# Daughter_Card_Schematic_v5.net
KiCad netlist of a schematic drawn in EAGLE
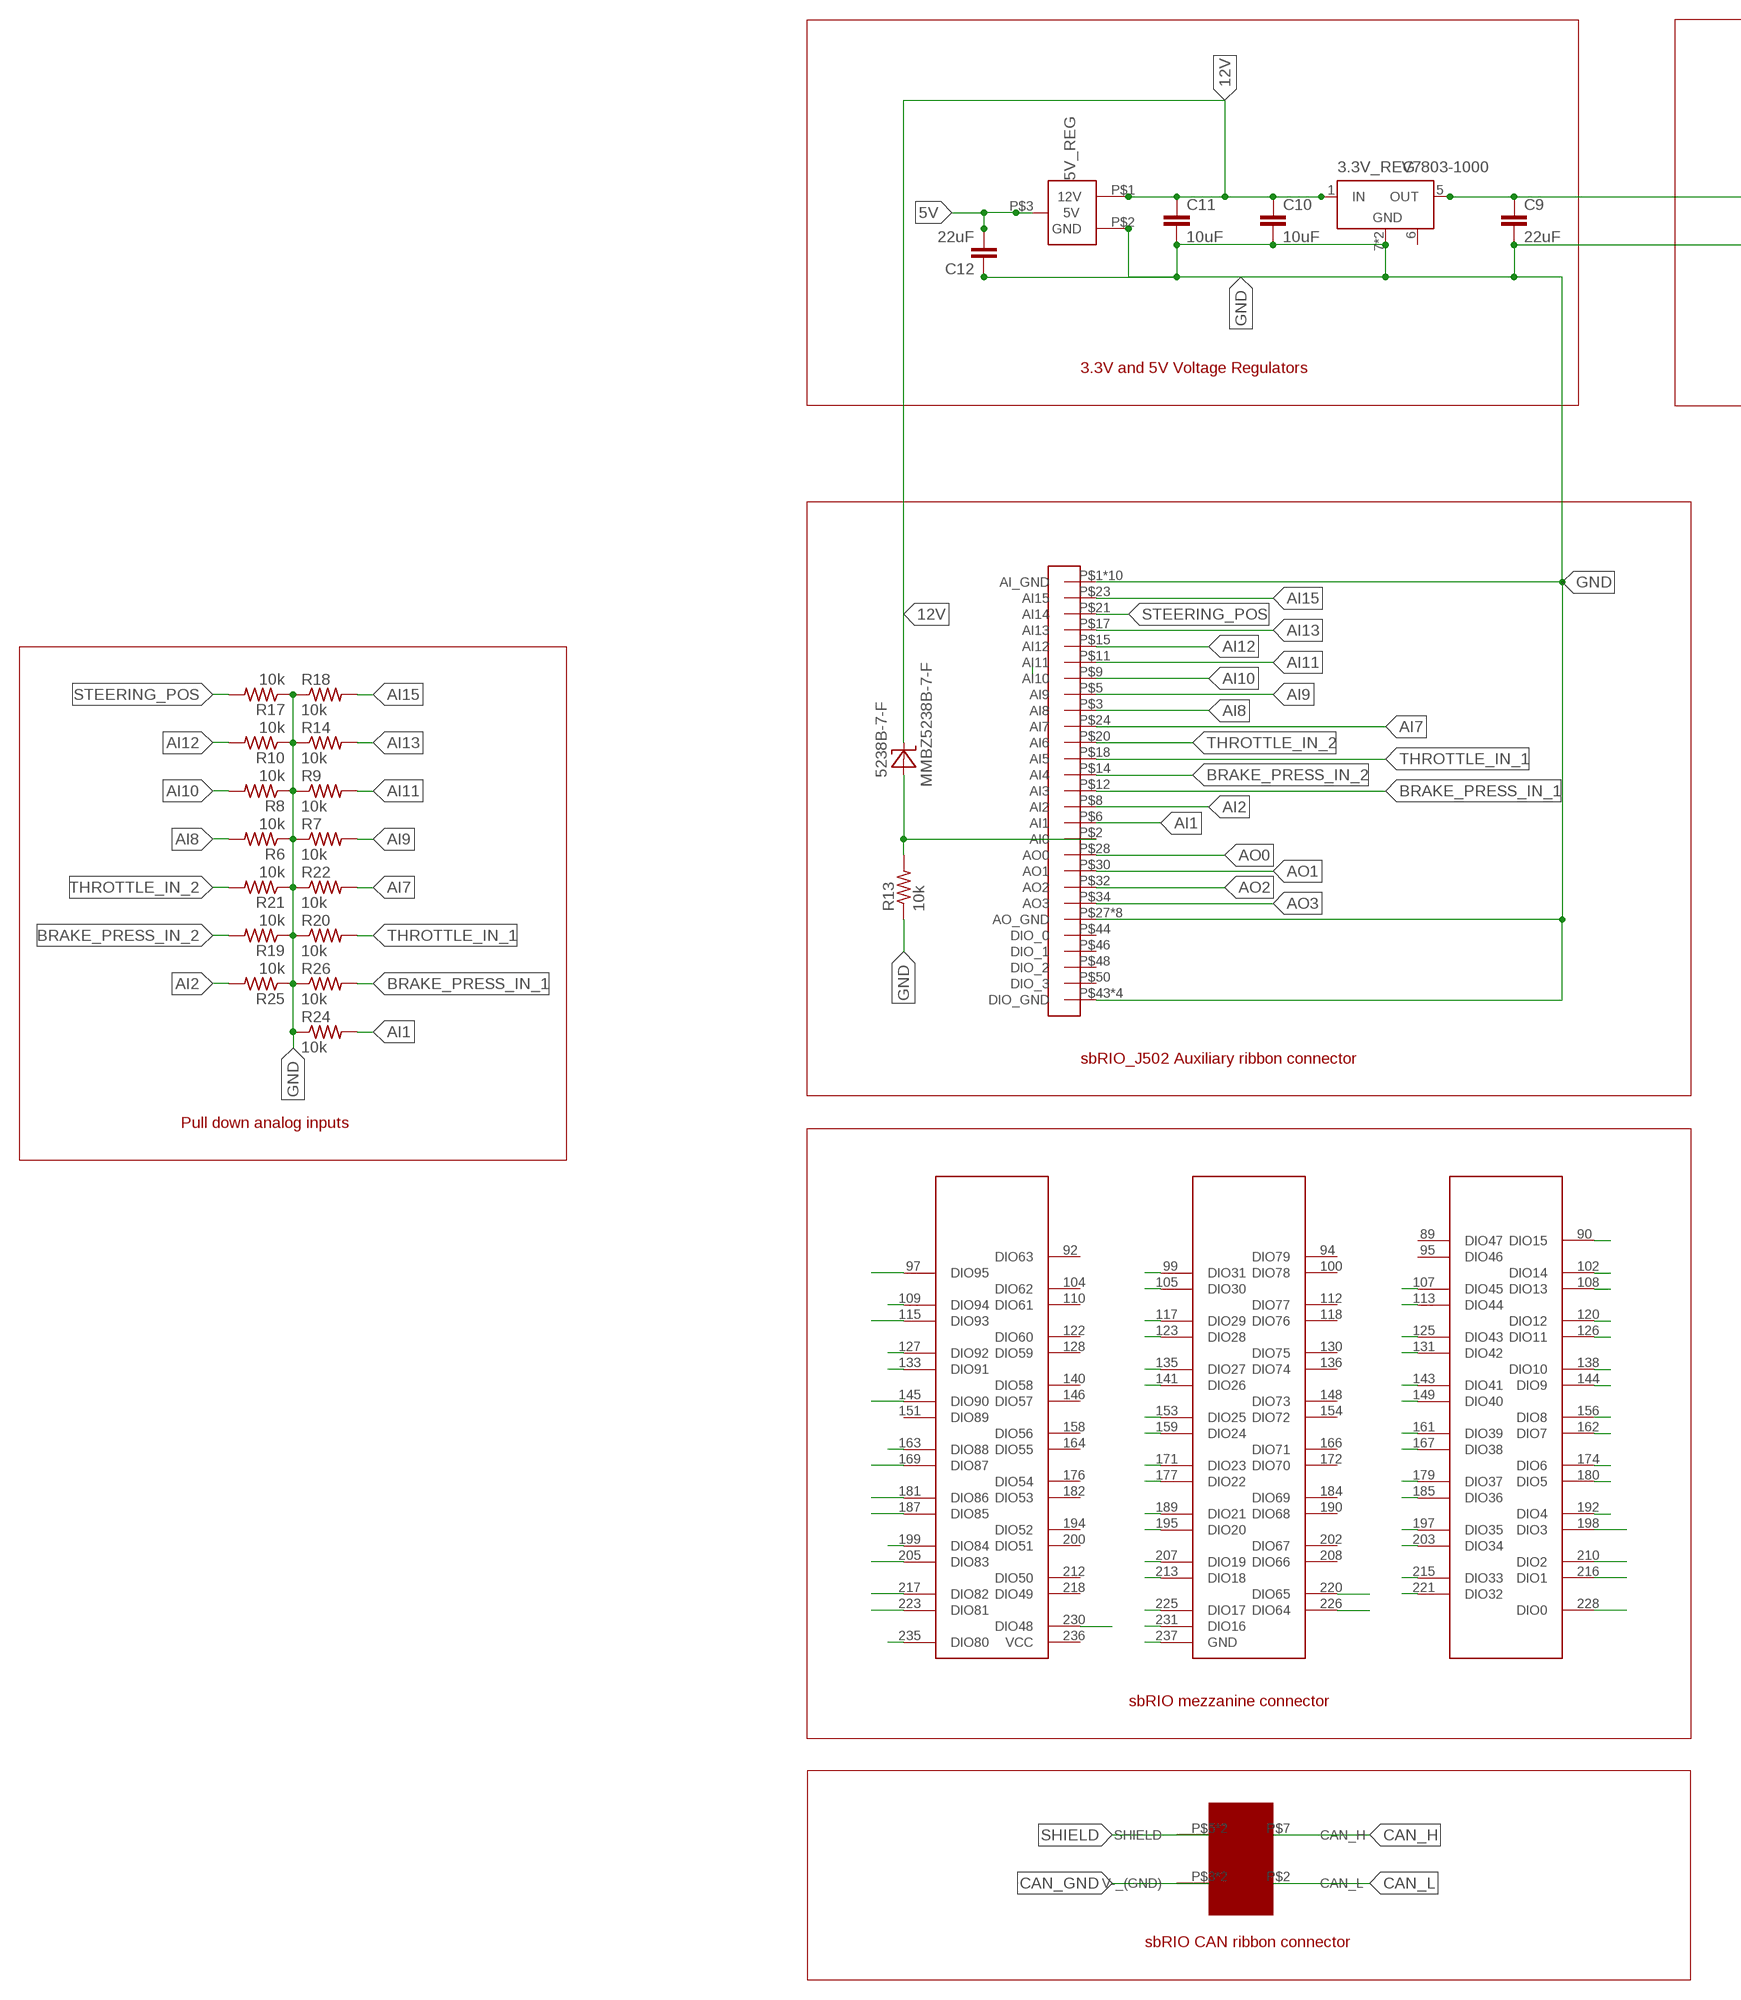
[diagram p0: schematic, sheet 1, part 1 of 2]
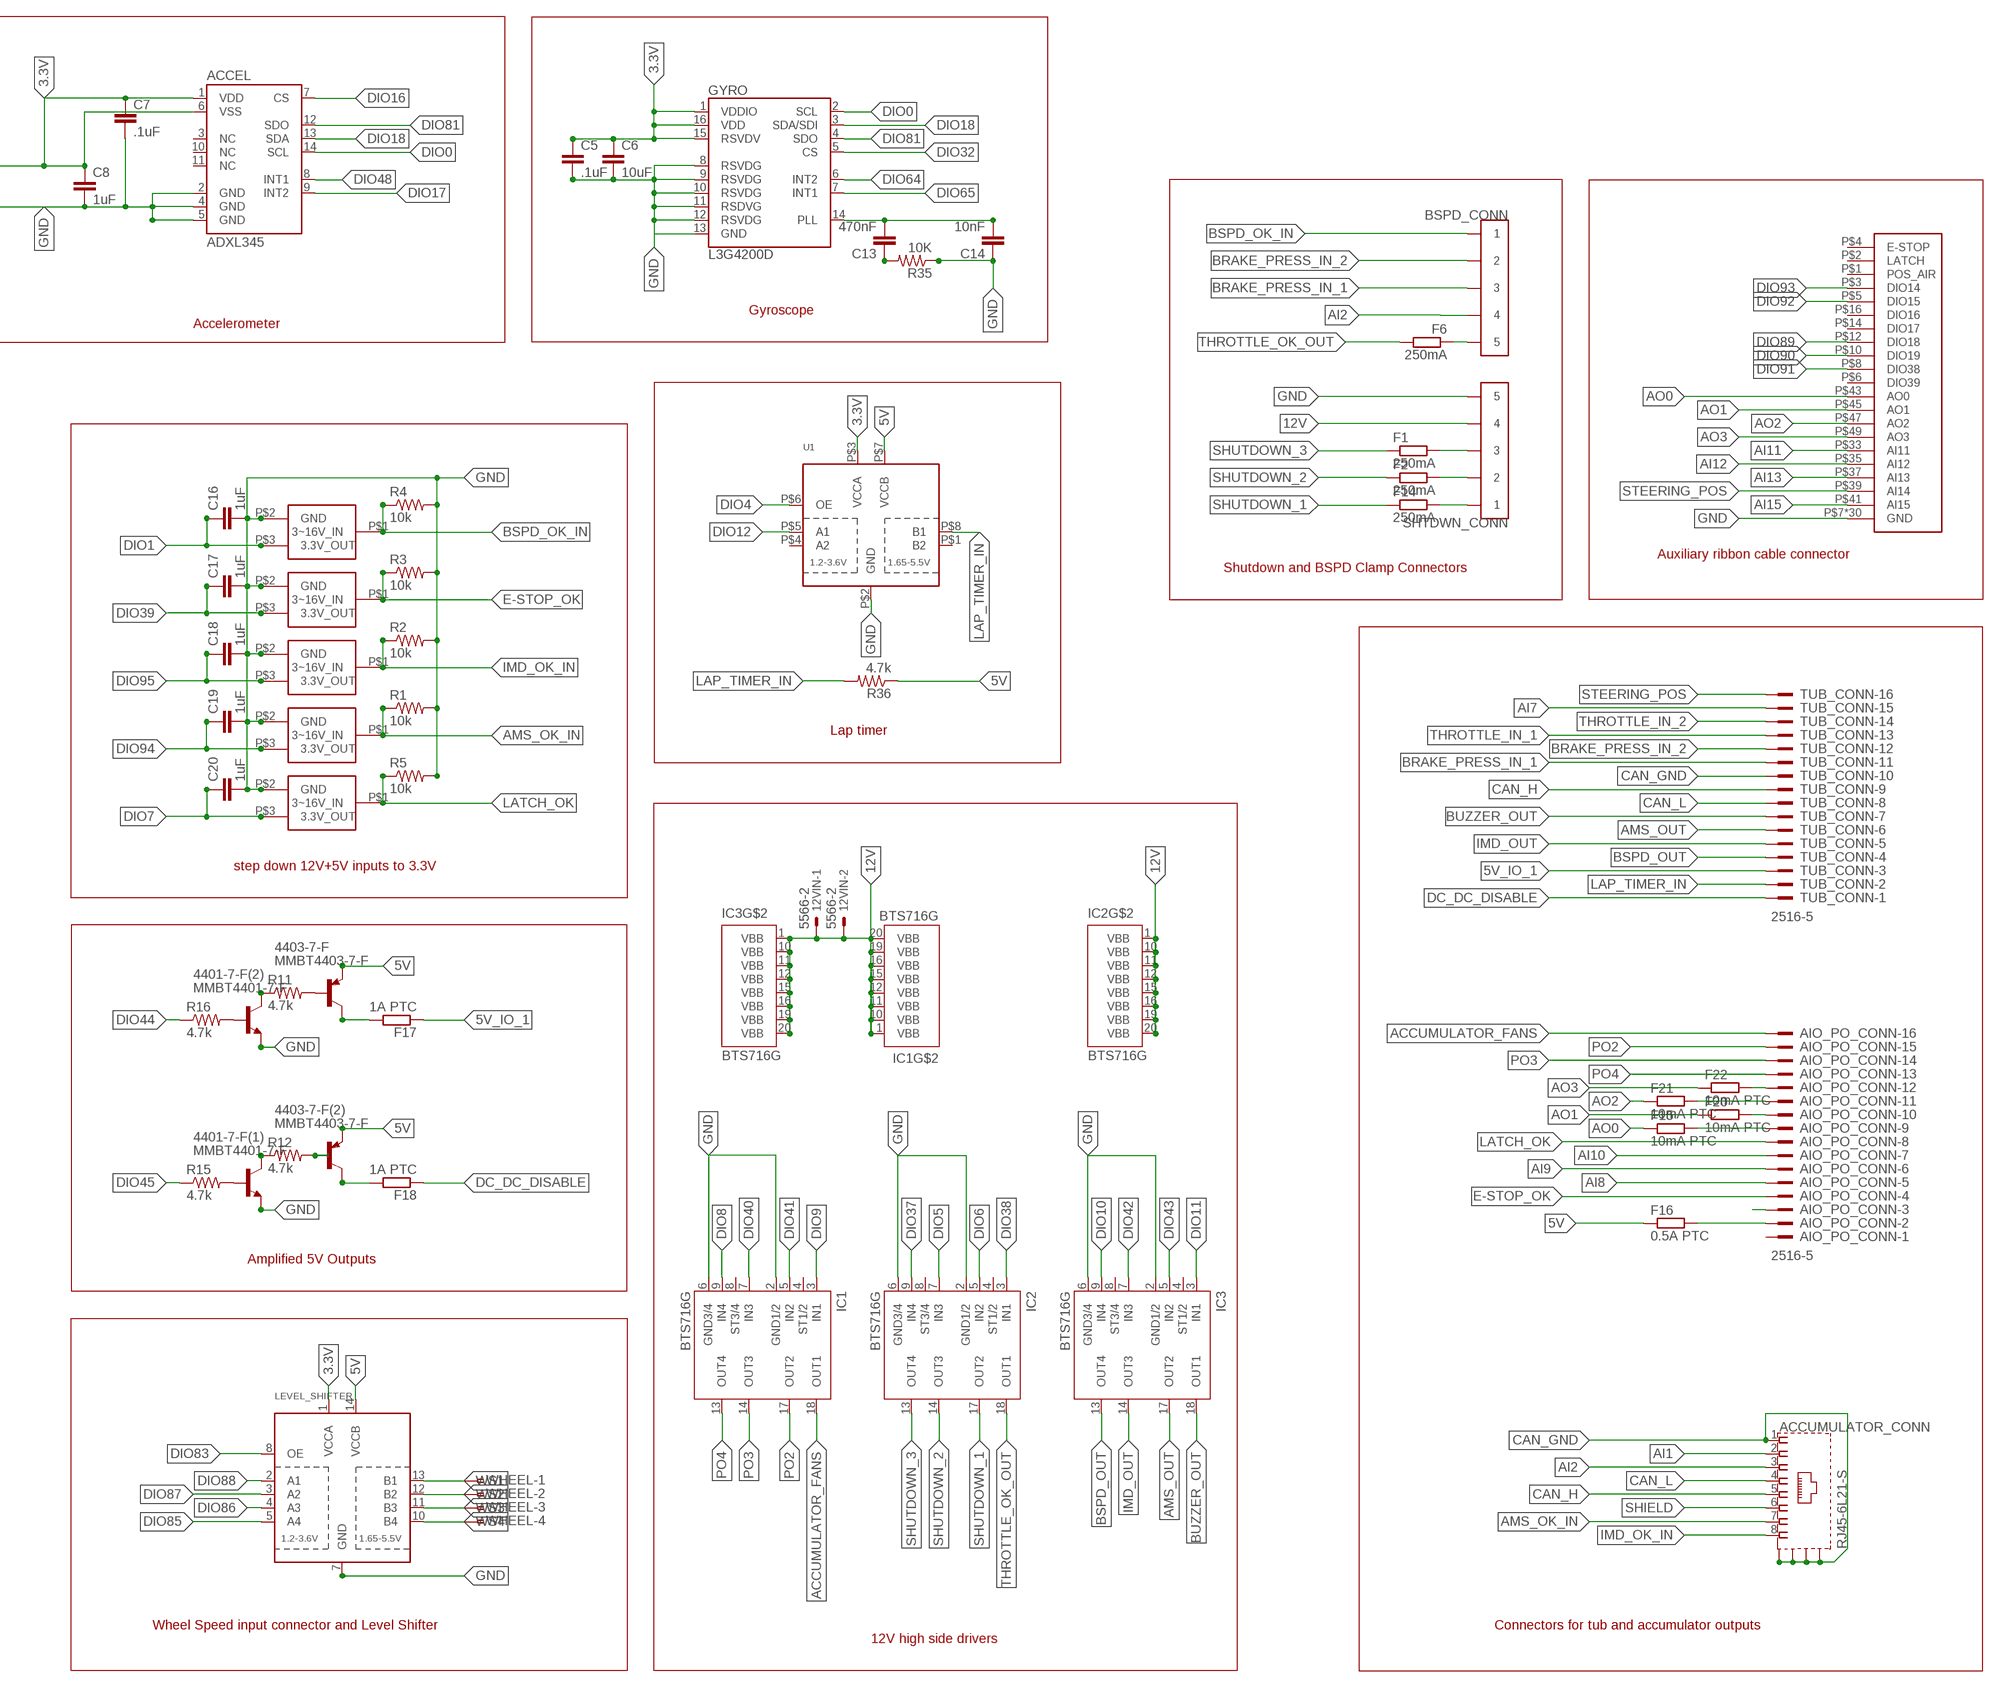
[diagram p1: schematic, sheet 1, part 2 of 2]

(export (version "E")
  (design (tool "Eeschema 10.0.6"))
  (components
    (comp (ref "3.3V_REG")
      (value "V7803-1000")
      (footprint "eagle-import:V78XX-1000")
      (libsource (lib "eagle-import") (part "V7803-1000"))
    )
    (comp (ref "5V_REG")
      (value "V78XX-1500")
      (footprint "eagle-import:V78XX-1500R")
      (libsource (lib "eagle-import") (part "V78XX-1500"))
    )
    (comp (ref "12VIN")
      (value "5566-2")
      (footprint "eagle-import:5566-2")
      (libsource (lib "eagle-import") (part "5566-2"))
    )
    (comp (ref "4401-7-F(1)")
      (value "MMBT4401-7-F")
      (footprint "eagle-import:SOT-23-3")
      (libsource (lib "eagle-import") (part "MMBT4401-7-F"))
    )
    (comp (ref "4401-7-F(2)")
      (value "MMBT4401-7-F")
      (footprint "eagle-import:SOT-23-3")
      (libsource (lib "eagle-import") (part "MMBT4401-7-F"))
    )
    (comp (ref "4403-7-F")
      (value "MMBT4403-7-F")
      (footprint "eagle-import:SOT-23-3")
      (libsource (lib "eagle-import") (part "MMBT4403-7-F"))
    )
    (comp (ref "4403-7-F(2)")
      (value "MMBT4403-7-F")
      (footprint "eagle-import:SOT-23-3")
      (libsource (lib "eagle-import") (part "MMBT4403-7-F"))
    )
    (comp (ref "5225-3.3M5-TR(5)")
      (value "MIC5225-3.3YM5-TR")
      (footprint "eagle-import:SOT-23-3")
      (libsource (lib "eagle-import") (part "MIC5225-3.3YM5-TR"))
    )
    (comp (ref "5238B-7-F")
      (value "MMBZ5238B-7-F")
      (footprint "eagle-import:SOT-23-3")
      (libsource (lib "eagle-import") (part "MMBZ5238B-7-F"))
    )
    (comp (ref "5525-3.3YM5-TR(1)")
      (value "MIC5225-3.3YM5-TR")
      (footprint "eagle-import:SOT-23-3")
      (libsource (lib "eagle-import") (part "MIC5225-3.3YM5-TR"))
    )
    (comp (ref "5525-3.3YM5-TR(2)")
      (value "MIC5225-3.3YM5-TR")
      (footprint "eagle-import:SOT-23-3")
      (libsource (lib "eagle-import") (part "MIC5225-3.3YM5-TR"))
    )
    (comp (ref "5525-3.3YM5-TR(3)")
      (value "MIC5225-3.3YM5-TR")
      (footprint "eagle-import:SOT-23-3")
      (libsource (lib "eagle-import") (part "MIC5225-3.3YM5-TR"))
    )
    (comp (ref "5525-3.3YM5-TR(4)")
      (value "MIC5225-3.3YM5-TR")
      (footprint "eagle-import:SOT-23-3")
      (libsource (lib "eagle-import") (part "MIC5225-3.3YM5-TR"))
    )
    (comp (ref "ACCEL")
      (value "ADXL345")
      (footprint "eagle-import:LGA14")
      (libsource (lib "eagle-import") (part "ADXL345"))
    )
    (comp (ref "ACCUMULATOR_CONN")
      (value "RJ45-6L21-S")
      (footprint "eagle-import:RJ45-SHIELD1")
      (libsource (lib "eagle-import") (part "RJ4521-S-6L"))
    )
    (comp (ref "AIO_PO_CONN")
      (value "2516-5")
      (footprint "eagle-import:PAK100_2500-5-16")
      (fields (field (name "MPN") "D2516-5002-AR"))
      (libsource (lib "eagle-import") (part "2516-5"))
    )
    (comp (ref "BSPD_CONN")
      (value "CONN_5")
      (footprint "eagle-import:CONNECTOR_5")
      (libsource (lib "eagle-import") (part "CONN_5"))
    )
    (comp (ref "C5")
      (value ".1uF")
      (footprint "eagle-import:0603-CAP")
      (libsource (lib "eagle-import") (part "CAP0603-CAP"))
    )
    (comp (ref "C6")
      (value "10uF")
      (footprint "eagle-import:0603-CAP")
      (libsource (lib "eagle-import") (part "CAP0603-CAP"))
    )
    (comp (ref "C7")
      (value ".1uF")
      (footprint "eagle-import:0603-CAP")
      (libsource (lib "eagle-import") (part "CAP0603-CAP"))
    )
    (comp (ref "C8")
      (value "1uF")
      (footprint "eagle-import:0603-CAP")
      (libsource (lib "eagle-import") (part "CAP0603-CAP"))
    )
    (comp (ref "C9")
      (value "22uF")
      (footprint "eagle-import:0603-CAP")
      (libsource (lib "eagle-import") (part "CAP0603-CAP"))
    )
    (comp (ref "C10")
      (value "10uF")
      (footprint "eagle-import:0603-CAP")
      (libsource (lib "eagle-import") (part "CAP0603-CAP"))
    )
    (comp (ref "C11")
      (value "10uF")
      (footprint "eagle-import:0603-CAP")
      (libsource (lib "eagle-import") (part "CAP0603-CAP"))
    )
    (comp (ref "C12")
      (value "22uF")
      (footprint "eagle-import:0603-CAP")
      (libsource (lib "eagle-import") (part "CAP0603-CAP"))
    )
    (comp (ref "C13")
      (value "470nF")
      (footprint "eagle-import:0603-CAP")
      (libsource (lib "eagle-import") (part "CAP0603-CAP"))
    )
    (comp (ref "C14")
      (value "10nF")
      (footprint "eagle-import:0603-CAP")
      (libsource (lib "eagle-import") (part "CAP0603-CAP"))
    )
    (comp (ref "C16")
      (value "1uF")
      (footprint "eagle-import:0603-CAP")
      (libsource (lib "eagle-import") (part "CAP0603-CAP"))
    )
    (comp (ref "C17")
      (value "1uF")
      (footprint "eagle-import:0603-CAP")
      (libsource (lib "eagle-import") (part "CAP0603-CAP"))
    )
    (comp (ref "C18")
      (value "1uF")
      (footprint "eagle-import:0603-CAP")
      (libsource (lib "eagle-import") (part "CAP0603-CAP"))
    )
    (comp (ref "C19")
      (value "1uF")
      (footprint "eagle-import:0603-CAP")
      (libsource (lib "eagle-import") (part "CAP0603-CAP"))
    )
    (comp (ref "C20")
      (value "1uF")
      (footprint "eagle-import:0603-CAP")
      (libsource (lib "eagle-import") (part "CAP0603-CAP"))
    )
    (comp (ref "F1")
      (value "250mA")
      (footprint "eagle-import:R0603")
      (libsource (lib "eagle-import") (part "R-EU_R0603"))
    )
    (comp (ref "F2")
      (value "250mA")
      (footprint "eagle-import:R0603")
      (libsource (lib "eagle-import") (part "R-EU_R0603"))
    )
    (comp (ref "F6")
      (value "250mA")
      (footprint "eagle-import:R0603")
      (libsource (lib "eagle-import") (part "R-EU_R0603"))
    )
    (comp (ref "F14")
      (value "250mA")
      (footprint "eagle-import:R0603")
      (libsource (lib "eagle-import") (part "R-EU_R0603"))
    )
    (comp (ref "F15")
      (value "10mA PTC")
      (footprint "eagle-import:R0402")
      (libsource (lib "eagle-import") (part "R-EU_R0402"))
    )
    (comp (ref "F16")
      (value "0.5A PTC")
      (footprint "eagle-import:R0603")
      (libsource (lib "eagle-import") (part "R-EU_R0603"))
    )
    (comp (ref "F17")
      (value "1A PTC")
      (footprint "eagle-import:R0603")
      (libsource (lib "eagle-import") (part "R-EU_R0603"))
    )
    (comp (ref "F18")
      (value "1A PTC")
      (footprint "eagle-import:R0603")
      (libsource (lib "eagle-import") (part "R-EU_R0603"))
    )
    (comp (ref "F20")
      (value "10mA PTC")
      (footprint "eagle-import:R0402")
      (libsource (lib "eagle-import") (part "R-EU_R0402"))
    )
    (comp (ref "F21")
      (value "10mA PTC")
      (footprint "eagle-import:R0402")
      (libsource (lib "eagle-import") (part "R-EU_R0402"))
    )
    (comp (ref "F22")
      (value "10mA PTC")
      (footprint "eagle-import:R0402")
      (libsource (lib "eagle-import") (part "R-EU_R0402"))
    )
    (comp (ref "GYRO")
      (value "L3G4200D")
      (footprint "eagle-import:LGA16-4X4")
      (libsource (lib "eagle-import") (part "L3G4200D"))
    )
    (comp (ref "IC1")
      (value "BTS716G")
      (footprint "eagle-import:PG-DSO-20")
      (libsource (lib "eagle-import") (part "BTS716G"))
    )
    (comp (ref "IC2")
      (value "BTS716G")
      (footprint "eagle-import:PG-DSO-20")
      (libsource (lib "eagle-import") (part "BTS716G"))
    )
    (comp (ref "IC3")
      (value "BTS716G")
      (footprint "eagle-import:PG-DSO-20")
      (libsource (lib "eagle-import") (part "BTS716G"))
    )
    (comp (ref "LEVEL_SHIFTER")
      (value "TXB0104PWR")
      (footprint "eagle-import:TSSOP14")
      (libsource (lib "eagle-import") (part "TXB0104PWR"))
    )
    (comp (ref "R1")
      (value "10k")
      (footprint "eagle-import:R0402")
      (libsource (lib "eagle-import") (part "R-US_R0402"))
    )
    (comp (ref "R2")
      (value "10k")
      (footprint "eagle-import:R0402")
      (libsource (lib "eagle-import") (part "R-US_R0402"))
    )
    (comp (ref "R3")
      (value "10k")
      (footprint "eagle-import:R0402")
      (libsource (lib "eagle-import") (part "R-US_R0402"))
    )
    (comp (ref "R4")
      (value "10k")
      (footprint "eagle-import:R0402")
      (libsource (lib "eagle-import") (part "R-US_R0402"))
    )
    (comp (ref "R5")
      (value "10k")
      (footprint "eagle-import:R0402")
      (libsource (lib "eagle-import") (part "R-US_R0402"))
    )
    (comp (ref "R6")
      (value "10k")
      (footprint "eagle-import:R0402")
      (libsource (lib "eagle-import") (part "R-US_R0402"))
    )
    (comp (ref "R7")
      (value "10k")
      (footprint "eagle-import:R0402")
      (libsource (lib "eagle-import") (part "R-US_R0402"))
    )
    (comp (ref "R8")
      (value "10k")
      (footprint "eagle-import:R0402")
      (libsource (lib "eagle-import") (part "R-US_R0402"))
    )
    (comp (ref "R9")
      (value "10k")
      (footprint "eagle-import:R0402")
      (libsource (lib "eagle-import") (part "R-US_R0402"))
    )
    (comp (ref "R10")
      (value "10k")
      (footprint "eagle-import:R0402")
      (libsource (lib "eagle-import") (part "R-US_R0402"))
    )
    (comp (ref "R11")
      (value "4.7k")
      (footprint "eagle-import:R0402")
      (libsource (lib "eagle-import") (part "R-US_R0402"))
    )
    (comp (ref "R12")
      (value "4.7k")
      (footprint "eagle-import:R0402")
      (libsource (lib "eagle-import") (part "R-US_R0402"))
    )
    (comp (ref "R13")
      (value "10k")
      (footprint "eagle-import:R0402")
      (libsource (lib "eagle-import") (part "R-US_R0402"))
    )
    (comp (ref "R14")
      (value "10k")
      (footprint "eagle-import:R0402")
      (libsource (lib "eagle-import") (part "R-US_R0402"))
    )
    (comp (ref "R15")
      (value "4.7k")
      (footprint "eagle-import:R0402")
      (libsource (lib "eagle-import") (part "R-US_R0402"))
    )
    (comp (ref "R16")
      (value "4.7k")
      (footprint "eagle-import:R0402")
      (libsource (lib "eagle-import") (part "R-US_R0402"))
    )
    (comp (ref "R17")
      (value "10k")
      (footprint "eagle-import:R0402")
      (libsource (lib "eagle-import") (part "R-US_R0402"))
    )
    (comp (ref "R18")
      (value "10k")
      (footprint "eagle-import:R0402")
      (libsource (lib "eagle-import") (part "R-US_R0402"))
    )
    (comp (ref "R19")
      (value "10k")
      (footprint "eagle-import:R0402")
      (libsource (lib "eagle-import") (part "R-US_R0402"))
    )
    (comp (ref "R20")
      (value "10k")
      (footprint "eagle-import:R0402")
      (libsource (lib "eagle-import") (part "R-US_R0402"))
    )
    (comp (ref "R21")
      (value "10k")
      (footprint "eagle-import:R0402")
      (libsource (lib "eagle-import") (part "R-US_R0402"))
    )
    (comp (ref "R22")
      (value "10k")
      (footprint "eagle-import:R0402")
      (libsource (lib "eagle-import") (part "R-US_R0402"))
    )
    (comp (ref "R24")
      (value "10k")
      (footprint "eagle-import:R0402")
      (libsource (lib "eagle-import") (part "R-US_R0402"))
    )
    (comp (ref "R25")
      (value "10k")
      (footprint "eagle-import:R0402")
      (libsource (lib "eagle-import") (part "R-US_R0402"))
    )
    (comp (ref "R26")
      (value "10k")
      (footprint "eagle-import:R0402")
      (libsource (lib "eagle-import") (part "R-US_R0402"))
    )
    (comp (ref "R35")
      (value "10K")
      (footprint "eagle-import:0603-RES")
      (libsource (lib "eagle-import") (part "RESISTOR0603-RES"))
    )
    (comp (ref "R36")
      (value "4.7k")
      (footprint "eagle-import:R0402")
      (libsource (lib "eagle-import") (part "R-US_R0402"))
    )
    (comp (ref "SBRIO_ANALOG")
      (value "SBRIO_MIO")
      (footprint "eagle-import:SBRIO_J502_J503")
      (libsource (lib "eagle-import") (part "SBRIO_MIO"))
    )
    (comp (ref "SBRIO_AUX")
      (value "SBRIO_AUX")
      (footprint "eagle-import:SBRIO_J502_J503")
      (libsource (lib "eagle-import") (part "SBRIO_AUX"))
    )
    (comp (ref "SBRIO_CAN")
      (value "SBRIO_W500")
      (footprint "eagle-import:SBRIO_W")
      (libsource (lib "eagle-import") (part "SBRIO_W500"))
    )
    (comp (ref "SBRIO_MEZZANINE")
      (value "SBRIO_RMC")
      (footprint "eagle-import:SEAM-40-XX.X-XX-06-X-A")
      (libsource (lib "eagle-import") (part "SBRIO_RMC"))
    )
    (comp (ref "SHTDWN_CONN")
      (value "CONN_5")
      (footprint "eagle-import:CONNECTOR_5")
      (libsource (lib "eagle-import") (part "CONN_5"))
    )
    (comp (ref "TUB_CONN")
      (value "2516-5")
      (footprint "eagle-import:PAK100_2500-5-16")
      (fields (field (name "MPN") "D2516-5002-AR"))
      (libsource (lib "eagle-import") (part "2516-5"))
    )
    (comp (ref "U1")
      (value "TXS0102")
      (footprint "eagle-import:VFSOP-8")
      (libsource (lib "eagle-import") (part "TXS0102"))
    )
    (comp (ref "WHEEL")
      (value "FTOP-4")
      (footprint "eagle-import:FTOP-4")
      (libsource (lib "eagle-import") (part "FTOP-4"))
    )
  )
  (nets
    (net (code "1") (name "/VCC") (class "Default")
      (node (ref "SBRIO_MEZZANINE") (pin "236") (pinfunction "VCC_236") (pintype "power_in"))
    )
    (net (code "2") (name "3.3V") (class "Default")
      (node (ref "3.3V_REG") (pin "5") (pinfunction "OUT_5") (pintype "output"))
      (node (ref "ACCEL") (pin "1") (pinfunction "VDD_1") (pintype "bidirectional"))
      (node (ref "ACCEL") (pin "6") (pinfunction "VSS_6") (pintype "bidirectional"))
      (node (ref "C5") (pin "1") (pinfunction "1_1") (pintype "passive"))
      (node (ref "C6") (pin "1") (pinfunction "1_1") (pintype "passive"))
      (node (ref "C7") (pin "1") (pinfunction "1_1") (pintype "passive"))
      (node (ref "C8") (pin "1") (pinfunction "1_1") (pintype "passive"))
      (node (ref "C9") (pin "1") (pinfunction "1_1") (pintype "passive"))
      (node (ref "GYRO") (pin "1") (pinfunction "VDDIO_1") (pintype "bidirectional"))
      (node (ref "GYRO") (pin "15") (pinfunction "RSVDV_15") (pintype "bidirectional"))
      (node (ref "GYRO") (pin "16") (pinfunction "VDD_16") (pintype "bidirectional"))
      (node (ref "LEVEL_SHIFTER") (pin "1") (pinfunction "VCCA_1") (pintype "bidirectional"))
      (node (ref "U1") (pin "P$3") (pinfunction "VCCA_P$3") (pintype "bidirectional"))
    )
    (net (code "3") (name "5V") (class "Default")
      (node (ref "4403-7-F") (pin "P$3") (pinfunction "E_P$3") (pintype "passive"))
      (node (ref "4403-7-F(2)") (pin "P$3") (pinfunction "E_P$3") (pintype "passive"))
      (node (ref "5V_REG") (pin "P$3") (pinfunction "5V_P$3") (pintype "power_in"))
      (node (ref "C12") (pin "2") (pinfunction "2_2") (pintype "passive"))
      (node (ref "F16") (pin "1") (pinfunction "1_1") (pintype "passive"))
      (node (ref "LEVEL_SHIFTER") (pin "14") (pinfunction "VCCB_14") (pintype "bidirectional"))
      (node (ref "R36") (pin "1") (pinfunction "1_1") (pintype "passive"))
      (node (ref "U1") (pin "P$7") (pinfunction "VCCB_P$7") (pintype "bidirectional"))
    )
    (net (code "4") (name "5V_IO_1") (class "Default")
      (node (ref "F17") (pin "1") (pinfunction "1_1") (pintype "passive"))
      (node (ref "TUB_CONN") (pin "3") (pinfunction "KL_3") (pintype "passive"))
    )
    (net (code "5") (name "12V") (class "Default")
      (node (ref "12VIN") (pin "1") (pinfunction "S_1") (pintype "passive"))
      (node (ref "12VIN") (pin "2") (pinfunction "S_2") (pintype "passive"))
      (node (ref "3.3V_REG") (pin "1") (pinfunction "IN_1") (pintype "input"))
      (node (ref "5238B-7-F") (pin "P$1") (pinfunction "C_P$1") (pintype "passive"))
      (node (ref "5V_REG") (pin "P$1") (pinfunction "12V_P$1") (pintype "power_in"))
      (node (ref "C10") (pin "1") (pinfunction "1_1") (pintype "passive"))
      (node (ref "C11") (pin "1") (pinfunction "1_1") (pintype "passive"))
      (node (ref "IC1") (pin "1") (pinfunction "VBB_1") (pintype "power_in"))
      (node (ref "IC1") (pin "10") (pinfunction "VBB_10") (pintype "power_in"))
      (node (ref "IC1") (pin "11") (pinfunction "VBB_11") (pintype "power_in"))
      (node (ref "IC1") (pin "12") (pinfunction "VBB_12") (pintype "power_in"))
      (node (ref "IC1") (pin "15") (pinfunction "VBB_15") (pintype "power_in"))
      (node (ref "IC1") (pin "16") (pinfunction "VBB_16") (pintype "power_in"))
      (node (ref "IC1") (pin "19") (pinfunction "VBB_19") (pintype "power_in"))
      (node (ref "IC1") (pin "20") (pinfunction "VBB_20") (pintype "power_in"))
      (node (ref "IC2") (pin "1") (pinfunction "VBB_1") (pintype "power_in"))
      (node (ref "IC2") (pin "10") (pinfunction "VBB_10") (pintype "power_in"))
      (node (ref "IC2") (pin "11") (pinfunction "VBB_11") (pintype "power_in"))
      (node (ref "IC2") (pin "12") (pinfunction "VBB_12") (pintype "power_in"))
      (node (ref "IC2") (pin "15") (pinfunction "VBB_15") (pintype "power_in"))
      (node (ref "IC2") (pin "16") (pinfunction "VBB_16") (pintype "power_in"))
      (node (ref "IC2") (pin "19") (pinfunction "VBB_19") (pintype "power_in"))
      (node (ref "IC2") (pin "20") (pinfunction "VBB_20") (pintype "power_in"))
      (node (ref "IC3") (pin "1") (pinfunction "VBB_1") (pintype "power_in"))
      (node (ref "IC3") (pin "10") (pinfunction "VBB_10") (pintype "power_in"))
      (node (ref "IC3") (pin "11") (pinfunction "VBB_11") (pintype "power_in"))
      (node (ref "IC3") (pin "12") (pinfunction "VBB_12") (pintype "power_in"))
      (node (ref "IC3") (pin "15") (pinfunction "VBB_15") (pintype "power_in"))
      (node (ref "IC3") (pin "16") (pinfunction "VBB_16") (pintype "power_in"))
      (node (ref "IC3") (pin "19") (pinfunction "VBB_19") (pintype "power_in"))
      (node (ref "IC3") (pin "20") (pinfunction "VBB_20") (pintype "power_in"))
      (node (ref "SHTDWN_CONN") (pin "7") (pinfunction "4_7") (pintype "bidirectional"))
      (node (ref "SHTDWN_CONN") (pin "8") (pinfunction "4_8") (pintype "bidirectional"))
    )
    (net (code "6") (name "ACCUMULATOR_FANS") (class "Default")
      (node (ref "AIO_PO_CONN") (pin "16") (pinfunction "KL_16") (pintype "passive"))
      (node (ref "IC1") (pin "18") (pinfunction "OUT1_18") (pintype "output"))
    )
    (net (code "7") (name "AI1") (class "Default")
      (node (ref "ACCUMULATOR_CONN") (pin "2") (pinfunction "2_2") (pintype "passive"))
      (node (ref "R24") (pin "2") (pinfunction "2_2") (pintype "passive"))
      (node (ref "SBRIO_ANALOG") (pin "P$6") (pinfunction "AI1_P$6") (pintype "input"))
    )
    (net (code "8") (name "AI2") (class "Default")
      (node (ref "ACCUMULATOR_CONN") (pin "3") (pinfunction "3_3") (pintype "passive"))
      (node (ref "BSPD_CONN") (pin "7") (pinfunction "4_7") (pintype "bidirectional"))
      (node (ref "BSPD_CONN") (pin "8") (pinfunction "4_8") (pintype "bidirectional"))
      (node (ref "R25") (pin "2") (pinfunction "2_2") (pintype "passive"))
      (node (ref "SBRIO_ANALOG") (pin "P$8") (pinfunction "AI2_P$8") (pintype "input"))
    )
    (net (code "9") (name "AI7") (class "Default")
      (node (ref "R22") (pin "2") (pinfunction "2_2") (pintype "passive"))
      (node (ref "SBRIO_ANALOG") (pin "P$24") (pinfunction "AI7_P$24") (pintype "input"))
      (node (ref "TUB_CONN") (pin "15") (pinfunction "KL_15") (pintype "passive"))
    )
    (net (code "10") (name "AI8") (class "Default")
      (node (ref "AIO_PO_CONN") (pin "5") (pinfunction "KL_5") (pintype "passive"))
      (node (ref "R6") (pin "2") (pinfunction "2_2") (pintype "passive"))
      (node (ref "SBRIO_ANALOG") (pin "P$3") (pinfunction "AI8_P$3") (pintype "input"))
    )
    (net (code "11") (name "AI9") (class "Default")
      (node (ref "AIO_PO_CONN") (pin "6") (pinfunction "KL_6") (pintype "passive"))
      (node (ref "R7") (pin "2") (pinfunction "2_2") (pintype "passive"))
      (node (ref "SBRIO_ANALOG") (pin "P$5") (pinfunction "AI9_P$5") (pintype "input"))
    )
    (net (code "12") (name "AI10") (class "Default")
      (node (ref "AIO_PO_CONN") (pin "7") (pinfunction "KL_7") (pintype "passive"))
      (node (ref "R8") (pin "2") (pinfunction "2_2") (pintype "passive"))
      (node (ref "SBRIO_ANALOG") (pin "P$9") (pinfunction "AI10_P$9") (pintype "input"))
    )
    (net (code "13") (name "AI11") (class "Default")
      (node (ref "R9") (pin "2") (pinfunction "2_2") (pintype "passive"))
      (node (ref "SBRIO_ANALOG") (pin "P$11") (pinfunction "AI11_P$11") (pintype "input"))
      (node (ref "SBRIO_AUX") (pin "P$33") (pinfunction "AI11_P$33") (pintype "bidirectional"))
    )
    (net (code "14") (name "AI12") (class "Default")
      (node (ref "R10") (pin "2") (pinfunction "2_2") (pintype "passive"))
      (node (ref "SBRIO_ANALOG") (pin "P$15") (pinfunction "AI12_P$15") (pintype "input"))
      (node (ref "SBRIO_AUX") (pin "P$35") (pinfunction "AI12_P$35") (pintype "bidirectional"))
    )
    (net (code "15") (name "AI13") (class "Default")
      (node (ref "R14") (pin "2") (pinfunction "2_2") (pintype "passive"))
      (node (ref "SBRIO_ANALOG") (pin "P$17") (pinfunction "AI13_P$17") (pintype "input"))
      (node (ref "SBRIO_AUX") (pin "P$37") (pinfunction "AI13_P$37") (pintype "bidirectional"))
    )
    (net (code "16") (name "AI15") (class "Default")
      (node (ref "R18") (pin "2") (pinfunction "2_2") (pintype "passive"))
      (node (ref "SBRIO_ANALOG") (pin "P$23") (pinfunction "AI15_P$23") (pintype "input"))
      (node (ref "SBRIO_AUX") (pin "P$41") (pinfunction "AI15_P$41") (pintype "bidirectional"))
    )
    (net (code "17") (name "AMS_OK_IN") (class "Default")
      (node (ref "5525-3.3YM5-TR(1)") (pin "P$1") (pinfunction "3~{16V_IN}_P$1") (pintype "bidirectional"))
      (node (ref "ACCUMULATOR_CONN") (pin "7") (pinfunction "7_7") (pintype "passive"))
      (node (ref "R1") (pin "1") (pinfunction "1_1") (pintype "passive"))
    )
    (net (code "18") (name "AMS_OUT") (class "Default")
      (node (ref "IC3") (pin "17") (pinfunction "OUT2_17") (pintype "output"))
      (node (ref "TUB_CONN") (pin "6") (pinfunction "KL_6") (pintype "passive"))
    )
    (net (code "19") (name "AO0") (class "Default")
      (node (ref "F15") (pin "1") (pinfunction "1_1") (pintype "passive"))
      (node (ref "SBRIO_ANALOG") (pin "P$28") (pinfunction "AO0_P$28") (pintype "output"))
      (node (ref "SBRIO_AUX") (pin "P$43") (pinfunction "AO0_P$43") (pintype "bidirectional"))
    )
    (net (code "20") (name "AO1") (class "Default")
      (node (ref "F20") (pin "1") (pinfunction "1_1") (pintype "passive"))
      (node (ref "SBRIO_ANALOG") (pin "P$30") (pinfunction "AO1_P$30") (pintype "output"))
      (node (ref "SBRIO_AUX") (pin "P$45") (pinfunction "AO1_P$45") (pintype "bidirectional"))
    )
    (net (code "21") (name "AO2") (class "Default")
      (node (ref "F21") (pin "1") (pinfunction "1_1") (pintype "passive"))
      (node (ref "SBRIO_ANALOG") (pin "P$32") (pinfunction "AO2_P$32") (pintype "output"))
      (node (ref "SBRIO_AUX") (pin "P$47") (pinfunction "AO2_P$47") (pintype "bidirectional"))
    )
    (net (code "22") (name "AO3") (class "Default")
      (node (ref "F22") (pin "1") (pinfunction "1_1") (pintype "passive"))
      (node (ref "SBRIO_ANALOG") (pin "P$34") (pinfunction "AO3_P$34") (pintype "output"))
      (node (ref "SBRIO_AUX") (pin "P$49") (pinfunction "AO3_P$49") (pintype "bidirectional"))
    )
    (net (code "23") (name "BRAKE_PRESS_IN_1") (class "Default")
      (node (ref "BSPD_CONN") (pin "5") (pinfunction "3_5") (pintype "bidirectional"))
      (node (ref "BSPD_CONN") (pin "6") (pinfunction "3_6") (pintype "bidirectional"))
      (node (ref "R26") (pin "2") (pinfunction "2_2") (pintype "passive"))
      (node (ref "SBRIO_ANALOG") (pin "P$12") (pinfunction "AI3_P$12") (pintype "input"))
      (node (ref "TUB_CONN") (pin "11") (pinfunction "KL_11") (pintype "passive"))
    )
    (net (code "24") (name "BRAKE_PRESS_IN_2") (class "Default")
      (node (ref "BSPD_CONN") (pin "3") (pinfunction "2_3") (pintype "bidirectional"))
      (node (ref "BSPD_CONN") (pin "4") (pinfunction "2_4") (pintype "bidirectional"))
      (node (ref "R19") (pin "2") (pinfunction "2_2") (pintype "passive"))
      (node (ref "SBRIO_ANALOG") (pin "P$14") (pinfunction "AI4_P$14") (pintype "input"))
      (node (ref "TUB_CONN") (pin "12") (pinfunction "KL_12") (pintype "passive"))
    )
    (net (code "25") (name "BSPD_OK_IN") (class "Default")
      (node (ref "5525-3.3YM5-TR(3)") (pin "P$1") (pinfunction "3~{16V_IN}_P$1") (pintype "bidirectional"))
      (node (ref "BSPD_CONN") (pin "1") (pinfunction "1_1") (pintype "bidirectional"))
      (node (ref "BSPD_CONN") (pin "2") (pinfunction "1_2") (pintype "bidirectional"))
      (node (ref "R4") (pin "1") (pinfunction "1_1") (pintype "passive"))
    )
    (net (code "26") (name "BSPD_OUT") (class "Default")
      (node (ref "IC3") (pin "13") (pinfunction "OUT4_13") (pintype "output"))
      (node (ref "TUB_CONN") (pin "4") (pinfunction "KL_4") (pintype "passive"))
    )
    (net (code "27") (name "BUZZER_OUT") (class "Default")
      (node (ref "IC3") (pin "18") (pinfunction "OUT1_18") (pintype "output"))
      (node (ref "TUB_CONN") (pin "7") (pinfunction "KL_7") (pintype "passive"))
    )
    (net (code "28") (name "CAN_GND") (class "Default")
      (node (ref "ACCUMULATOR_CONN") (pin "1") (pinfunction "1_1") (pintype "passive"))
      (node (ref "ACCUMULATOR_CONN") (pin "S1") (pinfunction "S_S1") (pintype "passive"))
      (node (ref "ACCUMULATOR_CONN") (pin "S2") (pinfunction "S_S2") (pintype "passive"))
      (node (ref "ACCUMULATOR_CONN") (pin "S3") (pinfunction "S_S3") (pintype "passive"))
      (node (ref "ACCUMULATOR_CONN") (pin "S4") (pinfunction "S_S4") (pintype "passive"))
      (node (ref "SBRIO_CAN") (pin "P$3") (pinfunction "V-_(GND)_P$3") (pintype "power_in"))
      (node (ref "SBRIO_CAN") (pin "P$6") (pinfunction "V-_(GND)_P$6") (pintype "power_in"))
      (node (ref "TUB_CONN") (pin "10") (pinfunction "KL_10") (pintype "passive"))
    )
    (net (code "29") (name "CAN_H") (class "Default")
      (node (ref "ACCUMULATOR_CONN") (pin "5") (pinfunction "5_5") (pintype "passive"))
      (node (ref "SBRIO_CAN") (pin "P$7") (pinfunction "CAN_H_P$7") (pintype "bidirectional"))
      (node (ref "TUB_CONN") (pin "9") (pinfunction "KL_9") (pintype "passive"))
    )
    (net (code "30") (name "CAN_L") (class "Default")
      (node (ref "ACCUMULATOR_CONN") (pin "4") (pinfunction "4_4") (pintype "passive"))
      (node (ref "SBRIO_CAN") (pin "P$2") (pinfunction "CAN_L_P$2") (pintype "bidirectional"))
      (node (ref "TUB_CONN") (pin "8") (pinfunction "KL_8") (pintype "passive"))
    )
    (net (code "31") (name "DC_DC_DISABLE") (class "Default")
      (node (ref "F18") (pin "1") (pinfunction "1_1") (pintype "passive"))
      (node (ref "TUB_CONN") (pin "1") (pinfunction "KL_1") (pintype "passive"))
    )
    (net (code "32") (name "DIO0") (class "Default")
      (node (ref "ACCEL") (pin "14") (pinfunction "SCL_14") (pintype "bidirectional"))
      (node (ref "GYRO") (pin "2") (pinfunction "SCL_2") (pintype "bidirectional"))
      (node (ref "SBRIO_MEZZANINE") (pin "228") (pinfunction "DIO0_228") (pintype "bidirectional"))
    )
    (net (code "33") (name "DIO1") (class "Default")
      (node (ref "5525-3.3YM5-TR(3)") (pin "P$3") (pinfunction "3.3V_OUT_P$3") (pintype "bidirectional"))
      (node (ref "C16") (pin "1") (pinfunction "1_1") (pintype "passive"))
      (node (ref "SBRIO_MEZZANINE") (pin "216") (pinfunction "DIO1_216") (pintype "bidirectional"))
    )
    (net (code "34") (name "DIO4") (class "Default")
      (node (ref "SBRIO_MEZZANINE") (pin "192") (pinfunction "DIO4_192") (pintype "bidirectional"))
      (node (ref "U1") (pin "P$6") (pinfunction "OE_P$6") (pintype "bidirectional"))
    )
    (net (code "35") (name "DIO5") (class "Default")
      (node (ref "IC2") (pin "7") (pinfunction "IN3_7") (pintype "input"))
      (node (ref "SBRIO_MEZZANINE") (pin "180") (pinfunction "DIO5_180") (pintype "bidirectional"))
    )
    (net (code "36") (name "DIO6") (class "Default")
      (node (ref "IC2") (pin "5") (pinfunction "IN2_5") (pintype "input"))
      (node (ref "SBRIO_MEZZANINE") (pin "174") (pinfunction "DIO6_174") (pintype "bidirectional"))
    )
    (net (code "37") (name "DIO7") (class "Default")
      (node (ref "5525-3.3YM5-TR(2)") (pin "P$3") (pinfunction "3.3V_OUT_P$3") (pintype "bidirectional"))
      (node (ref "C20") (pin "1") (pinfunction "1_1") (pintype "passive"))
      (node (ref "SBRIO_MEZZANINE") (pin "162") (pinfunction "DIO7_162") (pintype "bidirectional"))
    )
    (net (code "38") (name "DIO8") (class "Default")
      (node (ref "IC1") (pin "9") (pinfunction "IN4_9") (pintype "input"))
      (node (ref "SBRIO_MEZZANINE") (pin "156") (pinfunction "DIO8_156") (pintype "bidirectional"))
    )
    (net (code "39") (name "DIO9") (class "Default")
      (node (ref "IC1") (pin "3") (pinfunction "IN1_3") (pintype "input"))
      (node (ref "SBRIO_MEZZANINE") (pin "144") (pinfunction "DIO9_144") (pintype "bidirectional"))
    )
    (net (code "40") (name "DIO10") (class "Default")
      (node (ref "IC3") (pin "9") (pinfunction "IN4_9") (pintype "input"))
      (node (ref "SBRIO_MEZZANINE") (pin "138") (pinfunction "DIO10_138") (pintype "bidirectional"))
    )
    (net (code "41") (name "DIO11") (class "Default")
      (node (ref "IC3") (pin "3") (pinfunction "IN1_3") (pintype "input"))
      (node (ref "SBRIO_MEZZANINE") (pin "126") (pinfunction "DIO11_126") (pintype "bidirectional"))
    )
    (net (code "42") (name "DIO12") (class "Default")
      (node (ref "SBRIO_MEZZANINE") (pin "120") (pinfunction "DIO12_120") (pintype "bidirectional"))
      (node (ref "U1") (pin "P$5") (pinfunction "A1_P$5") (pintype "bidirectional"))
    )
    (net (code "43") (name "DIO16") (class "Default")
      (node (ref "ACCEL") (pin "7") (pinfunction "CS_7") (pintype "bidirectional"))
      (node (ref "SBRIO_MEZZANINE") (pin "231") (pinfunction "DIO16_231") (pintype "bidirectional"))
    )
    (net (code "44") (name "DIO17") (class "Default")
      (node (ref "ACCEL") (pin "9") (pinfunction "INT2_9") (pintype "bidirectional"))
      (node (ref "SBRIO_MEZZANINE") (pin "225") (pinfunction "DIO17_225") (pintype "bidirectional"))
    )
    (net (code "45") (name "DIO18") (class "Default")
      (node (ref "ACCEL") (pin "13") (pinfunction "SDA_13") (pintype "bidirectional"))
      (node (ref "GYRO") (pin "3") (pinfunction "SDA/SDI_3") (pintype "bidirectional"))
      (node (ref "SBRIO_MEZZANINE") (pin "213") (pinfunction "DIO18_213") (pintype "bidirectional"))
    )
    (net (code "46") (name "DIO32") (class "Default")
      (node (ref "GYRO") (pin "5") (pinfunction "CS_5") (pintype "bidirectional"))
      (node (ref "SBRIO_MEZZANINE") (pin "221") (pinfunction "DIO32_221") (pintype "bidirectional"))
    )
    (net (code "47") (name "DIO37") (class "Default")
      (node (ref "IC2") (pin "9") (pinfunction "IN4_9") (pintype "input"))
      (node (ref "SBRIO_MEZZANINE") (pin "179") (pinfunction "DIO37_179") (pintype "bidirectional"))
    )
    (net (code "48") (name "DIO38") (class "Default")
      (node (ref "IC2") (pin "3") (pinfunction "IN1_3") (pintype "input"))
      (node (ref "SBRIO_MEZZANINE") (pin "167") (pinfunction "DIO38_167") (pintype "bidirectional"))
    )
    (net (code "49") (name "DIO39") (class "Default")
      (node (ref "5525-3.3YM5-TR(4)") (pin "P$3") (pinfunction "3.3V_OUT_P$3") (pintype "bidirectional"))
      (node (ref "C17") (pin "1") (pinfunction "1_1") (pintype "passive"))
      (node (ref "SBRIO_MEZZANINE") (pin "161") (pinfunction "DIO39_161") (pintype "bidirectional"))
    )
    (net (code "50") (name "DIO40") (class "Default")
      (node (ref "IC1") (pin "7") (pinfunction "IN3_7") (pintype "input"))
      (node (ref "SBRIO_MEZZANINE") (pin "149") (pinfunction "DIO40_149") (pintype "bidirectional"))
    )
    (net (code "51") (name "DIO41") (class "Default")
      (node (ref "IC1") (pin "5") (pinfunction "IN2_5") (pintype "input"))
      (node (ref "SBRIO_MEZZANINE") (pin "143") (pinfunction "DIO41_143") (pintype "bidirectional"))
    )
    (net (code "52") (name "DIO42") (class "Default")
      (node (ref "IC3") (pin "7") (pinfunction "IN3_7") (pintype "input"))
      (node (ref "SBRIO_MEZZANINE") (pin "131") (pinfunction "DIO42_131") (pintype "bidirectional"))
    )
    (net (code "53") (name "DIO43") (class "Default")
      (node (ref "IC3") (pin "5") (pinfunction "IN2_5") (pintype "input"))
      (node (ref "SBRIO_MEZZANINE") (pin "125") (pinfunction "DIO43_125") (pintype "bidirectional"))
    )
    (net (code "54") (name "DIO44") (class "Default")
      (node (ref "R16") (pin "1") (pinfunction "1_1") (pintype "passive"))
      (node (ref "SBRIO_MEZZANINE") (pin "113") (pinfunction "DIO44_113") (pintype "bidirectional"))
    )
    (net (code "55") (name "DIO45") (class "Default")
      (node (ref "R15") (pin "1") (pinfunction "1_1") (pintype "passive"))
      (node (ref "SBRIO_MEZZANINE") (pin "107") (pinfunction "DIO45_107") (pintype "bidirectional"))
    )
    (net (code "56") (name "DIO48") (class "Default")
      (node (ref "ACCEL") (pin "8") (pinfunction "INT1_8") (pintype "bidirectional"))
      (node (ref "SBRIO_MEZZANINE") (pin "230") (pinfunction "DIO48_230") (pintype "bidirectional"))
    )
    (net (code "57") (name "DIO64") (class "Default")
      (node (ref "GYRO") (pin "6") (pinfunction "INT2_6") (pintype "bidirectional"))
      (node (ref "SBRIO_MEZZANINE") (pin "226") (pinfunction "DIO64_226") (pintype "bidirectional"))
    )
    (net (code "58") (name "DIO65") (class "Default")
      (node (ref "GYRO") (pin "7") (pinfunction "INT1_7") (pintype "bidirectional"))
      (node (ref "SBRIO_MEZZANINE") (pin "220") (pinfunction "DIO65_220") (pintype "bidirectional"))
    )
    (net (code "59") (name "DIO81") (class "Default")
      (node (ref "ACCEL") (pin "12") (pinfunction "SDO_12") (pintype "bidirectional"))
      (node (ref "GYRO") (pin "4") (pinfunction "SDO_4") (pintype "bidirectional"))
      (node (ref "SBRIO_MEZZANINE") (pin "223") (pinfunction "DIO81_223") (pintype "bidirectional"))
    )
    (net (code "60") (name "DIO83") (class "Default")
      (node (ref "LEVEL_SHIFTER") (pin "8") (pinfunction "OE_8") (pintype "bidirectional"))
      (node (ref "SBRIO_MEZZANINE") (pin "205") (pinfunction "DIO83_205") (pintype "bidirectional"))
    )
    (net (code "61") (name "DIO85") (class "Default")
      (node (ref "LEVEL_SHIFTER") (pin "5") (pinfunction "A4_5") (pintype "bidirectional"))
      (node (ref "SBRIO_MEZZANINE") (pin "187") (pinfunction "DIO85_187") (pintype "bidirectional"))
    )
    (net (code "62") (name "DIO86") (class "Default")
      (node (ref "LEVEL_SHIFTER") (pin "4") (pinfunction "A3_4") (pintype "bidirectional"))
      (node (ref "SBRIO_MEZZANINE") (pin "181") (pinfunction "DIO86_181") (pintype "bidirectional"))
    )
    (net (code "63") (name "DIO87") (class "Default")
      (node (ref "LEVEL_SHIFTER") (pin "3") (pinfunction "A2_3") (pintype "bidirectional"))
      (node (ref "SBRIO_MEZZANINE") (pin "169") (pinfunction "DIO87_169") (pintype "bidirectional"))
    )
    (net (code "64") (name "DIO88") (class "Default")
      (node (ref "LEVEL_SHIFTER") (pin "2") (pinfunction "A1_2") (pintype "bidirectional"))
      (node (ref "SBRIO_MEZZANINE") (pin "163") (pinfunction "DIO88_163") (pintype "bidirectional"))
    )
    (net (code "65") (name "DIO89") (class "Default")
      (node (ref "SBRIO_AUX") (pin "P$12") (pinfunction "DIO18_P$12") (pintype "bidirectional"))
    )
    (net (code "66") (name "DIO90") (class "Default")
      (node (ref "SBRIO_AUX") (pin "P$10") (pinfunction "DIO19_P$10") (pintype "bidirectional"))
      (node (ref "SBRIO_MEZZANINE") (pin "145") (pinfunction "DIO90_145") (pintype "bidirectional"))
    )
    (net (code "67") (name "DIO91") (class "Default")
      (node (ref "SBRIO_AUX") (pin "P$8") (pinfunction "DIO38_P$8") (pintype "bidirectional"))
      (node (ref "SBRIO_MEZZANINE") (pin "133") (pinfunction "DIO91_133") (pintype "bidirectional"))
    )
    (net (code "68") (name "DIO92") (class "Default")
      (node (ref "SBRIO_AUX") (pin "P$5") (pinfunction "DIO15_P$5") (pintype "bidirectional"))
      (node (ref "SBRIO_MEZZANINE") (pin "127") (pinfunction "DIO92_127") (pintype "bidirectional"))
    )
    (net (code "69") (name "DIO93") (class "Default")
      (node (ref "SBRIO_AUX") (pin "P$3") (pinfunction "DIO14_P$3") (pintype "bidirectional"))
      (node (ref "SBRIO_MEZZANINE") (pin "115") (pinfunction "DIO93_115") (pintype "bidirectional"))
    )
    (net (code "70") (name "DIO94") (class "Default")
      (node (ref "5525-3.3YM5-TR(1)") (pin "P$3") (pinfunction "3.3V_OUT_P$3") (pintype "bidirectional"))
      (node (ref "C19") (pin "1") (pinfunction "1_1") (pintype "passive"))
      (node (ref "SBRIO_MEZZANINE") (pin "109") (pinfunction "DIO94_109") (pintype "bidirectional"))
    )
    (net (code "71") (name "DIO95") (class "Default")
      (node (ref "5225-3.3M5-TR(5)") (pin "P$3") (pinfunction "3.3V_OUT_P$3") (pintype "bidirectional"))
      (node (ref "C18") (pin "1") (pinfunction "1_1") (pintype "passive"))
      (node (ref "SBRIO_MEZZANINE") (pin "97") (pinfunction "DIO95_97") (pintype "bidirectional"))
    )
    (net (code "72") (name "E-STOP_OK") (class "Default")
      (node (ref "5525-3.3YM5-TR(4)") (pin "P$1") (pinfunction "3~{16V_IN}_P$1") (pintype "bidirectional"))
      (node (ref "AIO_PO_CONN") (pin "4") (pinfunction "KL_4") (pintype "passive"))
      (node (ref "R3") (pin "1") (pinfunction "1_1") (pintype "passive"))
    )
    (net (code "73") (name "GND") (class "Default")
      (node (ref "3.3V_REG") (pin "7") (pinfunction "GND_7") (pintype "power_in"))
      (node (ref "3.3V_REG") (pin "9") (pinfunction "GND_9") (pintype "power_in"))
      (node (ref "4401-7-F(1)") (pin "P$3") (pinfunction "E_P$3") (pintype "passive"))
      (node (ref "4401-7-F(2)") (pin "P$3") (pinfunction "E_P$3") (pintype "passive"))
      (node (ref "5225-3.3M5-TR(5)") (pin "P$2") (pinfunction "GND_P$2") (pintype "bidirectional"))
      (node (ref "5525-3.3YM5-TR(1)") (pin "P$2") (pinfunction "GND_P$2") (pintype "bidirectional"))
      (node (ref "5525-3.3YM5-TR(2)") (pin "P$2") (pinfunction "GND_P$2") (pintype "bidirectional"))
      (node (ref "5525-3.3YM5-TR(3)") (pin "P$2") (pinfunction "GND_P$2") (pintype "bidirectional"))
      (node (ref "5525-3.3YM5-TR(4)") (pin "P$2") (pinfunction "GND_P$2") (pintype "bidirectional"))
      (node (ref "5V_REG") (pin "P$2") (pinfunction "GND_P$2") (pintype "power_in"))
      (node (ref "ACCEL") (pin "2") (pinfunction "GND_2") (pintype "bidirectional"))
      (node (ref "ACCEL") (pin "4") (pinfunction "GND_4") (pintype "bidirectional"))
      (node (ref "ACCEL") (pin "5") (pinfunction "GND_5") (pintype "bidirectional"))
      (node (ref "C10") (pin "2") (pinfunction "2_2") (pintype "passive"))
      (node (ref "C11") (pin "2") (pinfunction "2_2") (pintype "passive"))
      (node (ref "C12") (pin "1") (pinfunction "1_1") (pintype "passive"))
      (node (ref "C14") (pin "1") (pinfunction "1_1") (pintype "passive"))
      (node (ref "C16") (pin "2") (pinfunction "2_2") (pintype "passive"))
      (node (ref "C17") (pin "2") (pinfunction "2_2") (pintype "passive"))
      (node (ref "C18") (pin "2") (pinfunction "2_2") (pintype "passive"))
      (node (ref "C19") (pin "2") (pinfunction "2_2") (pintype "passive"))
      (node (ref "C20") (pin "2") (pinfunction "2_2") (pintype "passive"))
      (node (ref "C5") (pin "2") (pinfunction "2_2") (pintype "passive"))
      (node (ref "C6") (pin "2") (pinfunction "2_2") (pintype "passive"))
      (node (ref "C7") (pin "2") (pinfunction "2_2") (pintype "passive"))
      (node (ref "C8") (pin "2") (pinfunction "2_2") (pintype "passive"))
      (node (ref "C9") (pin "2") (pinfunction "2_2") (pintype "passive"))
      (node (ref "GYRO") (pin "10") (pinfunction "RSVDG_10") (pintype "bidirectional"))
      (node (ref "GYRO") (pin "11") (pinfunction "RSDVG_11") (pintype "bidirectional"))
      (node (ref "GYRO") (pin "12") (pinfunction "RSVDG_12") (pintype "bidirectional"))
      (node (ref "GYRO") (pin "13") (pinfunction "GND_13") (pintype "bidirectional"))
      (node (ref "GYRO") (pin "8") (pinfunction "RSVDG_8") (pintype "bidirectional"))
      (node (ref "GYRO") (pin "9") (pinfunction "RSVDG_9") (pintype "bidirectional"))
      (node (ref "IC1") (pin "2") (pinfunction "GND1/2_2") (pintype "input"))
      (node (ref "IC1") (pin "6") (pinfunction "GND3/4_6") (pintype "input"))
      (node (ref "IC2") (pin "2") (pinfunction "GND1/2_2") (pintype "input"))
      (node (ref "IC2") (pin "6") (pinfunction "GND3/4_6") (pintype "input"))
      (node (ref "IC3") (pin "2") (pinfunction "GND1/2_2") (pintype "input"))
      (node (ref "IC3") (pin "6") (pinfunction "GND3/4_6") (pintype "input"))
      (node (ref "LEVEL_SHIFTER") (pin "7") (pinfunction "GND_7") (pintype "bidirectional"))
      (node (ref "R1") (pin "2") (pinfunction "2_2") (pintype "passive"))
      (node (ref "R10") (pin "1") (pinfunction "1_1") (pintype "passive"))
      (node (ref "R13") (pin "1") (pinfunction "1_1") (pintype "passive"))
      (node (ref "R14") (pin "1") (pinfunction "1_1") (pintype "passive"))
      (node (ref "R17") (pin "1") (pinfunction "1_1") (pintype "passive"))
      (node (ref "R18") (pin "1") (pinfunction "1_1") (pintype "passive"))
      (node (ref "R19") (pin "1") (pinfunction "1_1") (pintype "passive"))
      (node (ref "R2") (pin "2") (pinfunction "2_2") (pintype "passive"))
      (node (ref "R20") (pin "1") (pinfunction "1_1") (pintype "passive"))
      (node (ref "R21") (pin "1") (pinfunction "1_1") (pintype "passive"))
      (node (ref "R22") (pin "1") (pinfunction "1_1") (pintype "passive"))
      (node (ref "R24") (pin "1") (pinfunction "1_1") (pintype "passive"))
      (node (ref "R25") (pin "1") (pinfunction "1_1") (pintype "passive"))
      (node (ref "R26") (pin "1") (pinfunction "1_1") (pintype "passive"))
      (node (ref "R3") (pin "2") (pinfunction "2_2") (pintype "passive"))
      (node (ref "R35") (pin "1") (pinfunction "1_1") (pintype "passive"))
      (node (ref "R4") (pin "2") (pinfunction "2_2") (pintype "passive"))
      (node (ref "R5") (pin "2") (pinfunction "2_2") (pintype "passive"))
      (node (ref "R6") (pin "1") (pinfunction "1_1") (pintype "passive"))
      (node (ref "R7") (pin "1") (pinfunction "1_1") (pintype "passive"))
      (node (ref "R8") (pin "1") (pinfunction "1_1") (pintype "passive"))
      (node (ref "R9") (pin "1") (pinfunction "1_1") (pintype "passive"))
      (node (ref "SBRIO_ANALOG") (pin "P$1") (pinfunction "AI_GND_P$1") (pintype "input"))
      (node (ref "SBRIO_ANALOG") (pin "P$10") (pinfunction "AI_GND_P$10") (pintype "input"))
      (node (ref "SBRIO_ANALOG") (pin "P$13") (pinfunction "AI_GND_P$13") (pintype "input"))
      (node (ref "SBRIO_ANALOG") (pin "P$16") (pinfunction "AI_GND_P$16") (pintype "input"))
      (node (ref "SBRIO_ANALOG") (pin "P$19") (pinfunction "AI_GND_P$19") (pintype "input"))
      (node (ref "SBRIO_ANALOG") (pin "P$22") (pinfunction "AI_GND_P$22") (pintype "input"))
      (node (ref "SBRIO_ANALOG") (pin "P$25") (pinfunction "AI_GND_P$25") (pintype "input"))
      (node (ref "SBRIO_ANALOG") (pin "P$26") (pinfunction "AI_GND_P$26") (pintype "input"))
      (node (ref "SBRIO_ANALOG") (pin "P$27") (pinfunction "AO_GND_P$27") (pintype "power_in"))
      (node (ref "SBRIO_ANALOG") (pin "P$29") (pinfunction "AO_GND_P$29") (pintype "power_in"))
      (node (ref "SBRIO_ANALOG") (pin "P$31") (pinfunction "AO_GND_P$31") (pintype "power_in"))
      (node (ref "SBRIO_ANALOG") (pin "P$33") (pinfunction "AO_GND_P$33") (pintype "power_in"))
      (node (ref "SBRIO_ANALOG") (pin "P$35") (pinfunction "AO_GND_P$35") (pintype "power_in"))
      (node (ref "SBRIO_ANALOG") (pin "P$37") (pinfunction "AO_GND_P$37") (pintype "power_in"))
      (node (ref "SBRIO_ANALOG") (pin "P$39") (pinfunction "AO_GND_P$39") (pintype "power_in"))
      (node (ref "SBRIO_ANALOG") (pin "P$4") (pinfunction "AI_GND_P$4") (pintype "input"))
      (node (ref "SBRIO_ANALOG") (pin "P$41") (pinfunction "AO_GND_P$41") (pintype "power_in"))
      (node (ref "SBRIO_ANALOG") (pin "P$43") (pinfunction "DIO_GND_P$43") (pintype "power_in"))
      (node (ref "SBRIO_ANALOG") (pin "P$45") (pinfunction "DIO_GND_P$45") (pintype "power_in"))
      (node (ref "SBRIO_ANALOG") (pin "P$47") (pinfunction "DIO_GND_P$47") (pintype "power_in"))
      (node (ref "SBRIO_ANALOG") (pin "P$49") (pinfunction "DIO_GND_P$49") (pintype "power_in"))
      (node (ref "SBRIO_ANALOG") (pin "P$7") (pinfunction "AI_GND_P$7") (pintype "input"))
      (node (ref "SBRIO_AUX") (pin "P$11") (pinfunction "GND_P$11") (pintype "bidirectional"))
      (node (ref "SBRIO_AUX") (pin "P$13") (pinfunction "GND_P$13") (pintype "bidirectional"))
      (node (ref "SBRIO_AUX") (pin "P$15") (pinfunction "GND_P$15") (pintype "bidirectional"))
      (node (ref "SBRIO_AUX") (pin "P$17") (pinfunction "GND_P$17") (pintype "bidirectional"))
      (node (ref "SBRIO_AUX") (pin "P$18") (pinfunction "GND_P$18") (pintype "bidirectional"))
      (node (ref "SBRIO_AUX") (pin "P$19") (pinfunction "GND_P$19") (pintype "bidirectional"))
      (node (ref "SBRIO_AUX") (pin "P$20") (pinfunction "GND_P$20") (pintype "bidirectional"))
      (node (ref "SBRIO_AUX") (pin "P$21") (pinfunction "GND_P$21") (pintype "bidirectional"))
      (node (ref "SBRIO_AUX") (pin "P$22") (pinfunction "GND_P$22") (pintype "bidirectional"))
      (node (ref "SBRIO_AUX") (pin "P$23") (pinfunction "GND_P$23") (pintype "bidirectional"))
      (node (ref "SBRIO_AUX") (pin "P$24") (pinfunction "GND_P$24") (pintype "bidirectional"))
      (node (ref "SBRIO_AUX") (pin "P$25") (pinfunction "GND_P$25") (pintype "bidirectional"))
      (node (ref "SBRIO_AUX") (pin "P$26") (pinfunction "GND_P$26") (pintype "bidirectional"))
      (node (ref "SBRIO_AUX") (pin "P$27") (pinfunction "GND_P$27") (pintype "bidirectional"))
      (node (ref "SBRIO_AUX") (pin "P$28") (pinfunction "GND_P$28") (pintype "bidirectional"))
      (node (ref "SBRIO_AUX") (pin "P$29") (pinfunction "GND_P$29") (pintype "bidirectional"))
      (node (ref "SBRIO_AUX") (pin "P$30") (pinfunction "GND_P$30") (pintype "bidirectional"))
      (node (ref "SBRIO_AUX") (pin "P$31") (pinfunction "GND_P$31") (pintype "bidirectional"))
      (node (ref "SBRIO_AUX") (pin "P$32") (pinfunction "GND_P$32") (pintype "bidirectional"))
      (node (ref "SBRIO_AUX") (pin "P$34") (pinfunction "GND_P$34") (pintype "bidirectional"))
      (node (ref "SBRIO_AUX") (pin "P$36") (pinfunction "GND_P$36") (pintype "bidirectional"))
      (node (ref "SBRIO_AUX") (pin "P$38") (pinfunction "GND_P$38") (pintype "bidirectional"))
      (node (ref "SBRIO_AUX") (pin "P$40") (pinfunction "GND_P$40") (pintype "bidirectional"))
      (node (ref "SBRIO_AUX") (pin "P$42") (pinfunction "GND_P$42") (pintype "bidirectional"))
      (node (ref "SBRIO_AUX") (pin "P$44") (pinfunction "GND_P$44") (pintype "bidirectional"))
      (node (ref "SBRIO_AUX") (pin "P$46") (pinfunction "GND_P$46") (pintype "bidirectional"))
      (node (ref "SBRIO_AUX") (pin "P$48") (pinfunction "GND_P$48") (pintype "bidirectional"))
      (node (ref "SBRIO_AUX") (pin "P$50") (pinfunction "GND_P$50") (pintype "bidirectional"))
      (node (ref "SBRIO_AUX") (pin "P$7") (pinfunction "GND_P$7") (pintype "bidirectional"))
      (node (ref "SBRIO_AUX") (pin "P$9") (pinfunction "GND_P$9") (pintype "bidirectional"))
      (node (ref "SBRIO_MEZZANINE") (pin "237") (pinfunction "GND_237") (pintype "power_in"))
      (node (ref "SHTDWN_CONN") (pin "10") (pinfunction "5_10") (pintype "bidirectional"))
      (node (ref "SHTDWN_CONN") (pin "9") (pinfunction "5_9") (pintype "bidirectional"))
      (node (ref "U1") (pin "P$2") (pinfunction "GND_P$2") (pintype "bidirectional"))
    )
    (net (code "74") (name "IMD_OK_IN") (class "Default")
      (node (ref "5225-3.3M5-TR(5)") (pin "P$1") (pinfunction "3~{16V_IN}_P$1") (pintype "bidirectional"))
      (node (ref "ACCUMULATOR_CONN") (pin "8") (pinfunction "8_8") (pintype "passive"))
      (node (ref "R2") (pin "1") (pinfunction "1_1") (pintype "passive"))
    )
    (net (code "75") (name "IMD_OUT") (class "Default")
      (node (ref "IC3") (pin "14") (pinfunction "OUT3_14") (pintype "output"))
      (node (ref "TUB_CONN") (pin "5") (pinfunction "KL_5") (pintype "passive"))
    )
    (net (code "76") (name "LAP_TIMER_IN") (class "Default")
      (node (ref "R36") (pin "2") (pinfunction "2_2") (pintype "passive"))
      (node (ref "TUB_CONN") (pin "2") (pinfunction "KL_2") (pintype "passive"))
      (node (ref "U1") (pin "P$8") (pinfunction "B1_P$8") (pintype "bidirectional"))
    )
    (net (code "77") (name "LATCH_OK") (class "Default")
      (node (ref "5525-3.3YM5-TR(2)") (pin "P$1") (pinfunction "3~{16V_IN}_P$1") (pintype "bidirectional"))
      (node (ref "AIO_PO_CONN") (pin "8") (pinfunction "KL_8") (pintype "passive"))
      (node (ref "R5") (pin "1") (pinfunction "1_1") (pintype "passive"))
    )
    (net (code "78") (name "Net-(4401-7-F(1)-B)") (class "Default")
      (node (ref "4401-7-F(1)") (pin "P$2") (pinfunction "B_P$2") (pintype "passive"))
      (node (ref "R15") (pin "2") (pinfunction "2_2") (pintype "passive"))
    )
    (net (code "79") (name "Net-(4401-7-F(1)-C)") (class "Default")
      (node (ref "4401-7-F(1)") (pin "P$1") (pinfunction "C_P$1") (pintype "passive"))
      (node (ref "R12") (pin "1") (pinfunction "1_1") (pintype "passive"))
    )
    (net (code "80") (name "Net-(4401-7-F(2)-B)") (class "Default")
      (node (ref "4401-7-F(2)") (pin "P$2") (pinfunction "B_P$2") (pintype "passive"))
      (node (ref "R16") (pin "2") (pinfunction "2_2") (pintype "passive"))
    )
    (net (code "81") (name "Net-(4401-7-F(2)-C)") (class "Default")
      (node (ref "4401-7-F(2)") (pin "P$1") (pinfunction "C_P$1") (pintype "passive"))
      (node (ref "R11") (pin "1") (pinfunction "1_1") (pintype "passive"))
    )
    (net (code "82") (name "Net-(4403-7-F(2)-B)") (class "Default")
      (node (ref "4403-7-F(2)") (pin "P$2") (pinfunction "B_P$2") (pintype "passive"))
      (node (ref "R12") (pin "2") (pinfunction "2_2") (pintype "passive"))
    )
    (net (code "83") (name "Net-(4403-7-F(2)-C)") (class "Default")
      (node (ref "4403-7-F(2)") (pin "P$1") (pinfunction "C_P$1") (pintype "passive"))
      (node (ref "F18") (pin "2") (pinfunction "2_2") (pintype "passive"))
    )
    (net (code "84") (name "Net-(4403-7-F-B)") (class "Default")
      (node (ref "4403-7-F") (pin "P$2") (pinfunction "B_P$2") (pintype "passive"))
      (node (ref "R11") (pin "2") (pinfunction "2_2") (pintype "passive"))
    )
    (net (code "85") (name "Net-(4403-7-F-C)") (class "Default")
      (node (ref "4403-7-F") (pin "P$1") (pinfunction "C_P$1") (pintype "passive"))
      (node (ref "F17") (pin "2") (pinfunction "2_2") (pintype "passive"))
    )
    (net (code "86") (name "Net-(5238B-7-F-A)") (class "Default")
      (node (ref "5238B-7-F") (pin "P$2") (pinfunction "A_P$2") (pintype "passive"))
      (node (ref "R13") (pin "2") (pinfunction "2_2") (pintype "passive"))
      (node (ref "SBRIO_ANALOG") (pin "P$2") (pinfunction "AI0_P$2") (pintype "input"))
    )
    (net (code "87") (name "Net-(AIO_PO_CONNB-KL)") (class "Default")
      (node (ref "AIO_PO_CONN") (pin "10") (pinfunction "KL_10") (pintype "passive"))
      (node (ref "F20") (pin "2") (pinfunction "2_2") (pintype "passive"))
    )
    (net (code "88") (name "Net-(AIO_PO_CONNC-KL)") (class "Default")
      (node (ref "AIO_PO_CONN") (pin "11") (pinfunction "KL_11") (pintype "passive"))
      (node (ref "F21") (pin "2") (pinfunction "2_2") (pintype "passive"))
    )
    (net (code "89") (name "Net-(AIO_PO_CONND-KL)") (class "Default")
      (node (ref "AIO_PO_CONN") (pin "12") (pinfunction "KL_12") (pintype "passive"))
      (node (ref "F22") (pin "2") (pinfunction "2_2") (pintype "passive"))
    )
    (net (code "90") (name "Net-(AIO_PO_CONNI-KL)") (class "Default")
      (node (ref "AIO_PO_CONN") (pin "2") (pinfunction "KL_2") (pintype "passive"))
      (node (ref "F16") (pin "2") (pinfunction "2_2") (pintype "passive"))
    )
    (net (code "91") (name "Net-(AIO_PO_CONNP-KL)") (class "Default")
      (node (ref "AIO_PO_CONN") (pin "9") (pinfunction "KL_9") (pintype "passive"))
      (node (ref "F15") (pin "2") (pinfunction "2_2") (pintype "passive"))
    )
    (net (code "92") (name "Net-(BSPD_CONN-5-Pad10)") (class "Default")
      (node (ref "BSPD_CONN") (pin "10") (pinfunction "5_10") (pintype "bidirectional"))
      (node (ref "BSPD_CONN") (pin "9") (pinfunction "5_9") (pintype "bidirectional"))
      (node (ref "F6") (pin "1") (pinfunction "1_1") (pintype "passive"))
    )
    (net (code "93") (name "Net-(C13-Pad1)") (class "Default")
      (node (ref "C13") (pin "1") (pinfunction "1_1") (pintype "passive"))
      (node (ref "R35") (pin "2") (pinfunction "2_2") (pintype "passive"))
    )
    (net (code "94") (name "Net-(F1-Pad2)") (class "Default")
      (node (ref "F1") (pin "2") (pinfunction "2_2") (pintype "passive"))
      (node (ref "SHTDWN_CONN") (pin "5") (pinfunction "3_5") (pintype "bidirectional"))
      (node (ref "SHTDWN_CONN") (pin "6") (pinfunction "3_6") (pintype "bidirectional"))
    )
    (net (code "95") (name "Net-(F2-Pad2)") (class "Default")
      (node (ref "F2") (pin "2") (pinfunction "2_2") (pintype "passive"))
      (node (ref "SHTDWN_CONN") (pin "3") (pinfunction "2_3") (pintype "bidirectional"))
      (node (ref "SHTDWN_CONN") (pin "4") (pinfunction "2_4") (pintype "bidirectional"))
    )
    (net (code "96") (name "Net-(F14-Pad2)") (class "Default")
      (node (ref "F14") (pin "2") (pinfunction "2_2") (pintype "passive"))
      (node (ref "SHTDWN_CONN") (pin "1") (pinfunction "1_1") (pintype "bidirectional"))
      (node (ref "SHTDWN_CONN") (pin "2") (pinfunction "1_2") (pintype "bidirectional"))
    )
    (net (code "97") (name "Net-(GYRO-PLL)") (class "Default")
      (node (ref "C13") (pin "2") (pinfunction "2_2") (pintype "passive"))
      (node (ref "C14") (pin "2") (pinfunction "2_2") (pintype "passive"))
      (node (ref "GYRO") (pin "14") (pinfunction "PLL_14") (pintype "bidirectional"))
    )
    (net (code "98") (name "PO2") (class "Default")
      (node (ref "AIO_PO_CONN") (pin "15") (pinfunction "KL_15") (pintype "passive"))
      (node (ref "IC1") (pin "17") (pinfunction "OUT2_17") (pintype "output"))
    )
    (net (code "99") (name "PO3") (class "Default")
      (node (ref "AIO_PO_CONN") (pin "14") (pinfunction "KL_14") (pintype "passive"))
      (node (ref "IC1") (pin "14") (pinfunction "OUT3_14") (pintype "output"))
    )
    (net (code "100") (name "PO4") (class "Default")
      (node (ref "AIO_PO_CONN") (pin "13") (pinfunction "KL_13") (pintype "passive"))
      (node (ref "IC1") (pin "13") (pinfunction "OUT4_13") (pintype "output"))
    )
    (net (code "101") (name "SHIELD") (class "Default")
      (node (ref "ACCUMULATOR_CONN") (pin "6") (pinfunction "6_6") (pintype "passive"))
      (node (ref "SBRIO_CAN") (pin "P$10") (pinfunction "SHIELD_P$10") (pintype "power_in"))
      (node (ref "SBRIO_CAN") (pin "P$5") (pinfunction "SHIELD_P$5") (pintype "power_in"))
    )
    (net (code "102") (name "SHUTDOWN_1") (class "Default")
      (node (ref "F14") (pin "1") (pinfunction "1_1") (pintype "passive"))
      (node (ref "IC2") (pin "17") (pinfunction "OUT2_17") (pintype "output"))
    )
    (net (code "103") (name "SHUTDOWN_2") (class "Default")
      (node (ref "F2") (pin "1") (pinfunction "1_1") (pintype "passive"))
      (node (ref "IC2") (pin "14") (pinfunction "OUT3_14") (pintype "output"))
    )
    (net (code "104") (name "SHUTDOWN_3") (class "Default")
      (node (ref "F1") (pin "1") (pinfunction "1_1") (pintype "passive"))
      (node (ref "IC2") (pin "13") (pinfunction "OUT4_13") (pintype "output"))
    )
    (net (code "105") (name "STEERING_POS") (class "Default")
      (node (ref "R17") (pin "2") (pinfunction "2_2") (pintype "passive"))
      (node (ref "SBRIO_ANALOG") (pin "P$21") (pinfunction "AI14_P$21") (pintype "input"))
      (node (ref "SBRIO_AUX") (pin "P$39") (pinfunction "AI14_P$39") (pintype "bidirectional"))
      (node (ref "TUB_CONN") (pin "16") (pinfunction "KL_16") (pintype "passive"))
    )
    (net (code "106") (name "THROTTLE_IN_1") (class "Default")
      (node (ref "R20") (pin "2") (pinfunction "2_2") (pintype "passive"))
      (node (ref "SBRIO_ANALOG") (pin "P$18") (pinfunction "AI5_P$18") (pintype "input"))
      (node (ref "TUB_CONN") (pin "13") (pinfunction "KL_13") (pintype "passive"))
    )
    (net (code "107") (name "THROTTLE_IN_2") (class "Default")
      (node (ref "R21") (pin "2") (pinfunction "2_2") (pintype "passive"))
      (node (ref "SBRIO_ANALOG") (pin "P$20") (pinfunction "AI6_P$20") (pintype "input"))
      (node (ref "TUB_CONN") (pin "14") (pinfunction "KL_14") (pintype "passive"))
    )
    (net (code "108") (name "THROTTLE_OK_OUT") (class "Default")
      (node (ref "F6") (pin "2") (pinfunction "2_2") (pintype "passive"))
      (node (ref "IC2") (pin "18") (pinfunction "OUT1_18") (pintype "output"))
    )
    (net (code "109") (name "WS1") (class "Default")
      (node (ref "LEVEL_SHIFTER") (pin "13") (pinfunction "B1_13") (pintype "bidirectional"))
      (node (ref "WHEEL") (pin "1") (pinfunction "1_1") (pintype "passive"))
    )
    (net (code "110") (name "WS2") (class "Default")
      (node (ref "LEVEL_SHIFTER") (pin "12") (pinfunction "B2_12") (pintype "bidirectional"))
      (node (ref "WHEEL") (pin "2") (pinfunction "1_2") (pintype "passive"))
    )
    (net (code "111") (name "WS3") (class "Default")
      (node (ref "LEVEL_SHIFTER") (pin "11") (pinfunction "B3_11") (pintype "bidirectional"))
      (node (ref "WHEEL") (pin "3") (pinfunction "1_3") (pintype "passive"))
    )
    (net (code "112") (name "WS4") (class "Default")
      (node (ref "LEVEL_SHIFTER") (pin "10") (pinfunction "B4_10") (pintype "bidirectional"))
      (node (ref "WHEEL") (pin "4") (pinfunction "1_4") (pintype "passive"))
    )
    (net (code "113") (name "unconnected-(3.3V_REG-Pad6)") (class "Default")
      (node (ref "3.3V_REG") (pin "6") (pinfunction "6_6") (pintype "bidirectional"))
    )
    (net (code "114") (name "unconnected-(ACCEL-NC-Pad3)") (class "Default")
      (node (ref "ACCEL") (pin "3") (pinfunction "NC_3") (pintype "bidirectional"))
    )
    (net (code "115") (name "unconnected-(ACCEL-NC-Pad10)") (class "Default")
      (node (ref "ACCEL") (pin "10") (pinfunction "NC_10") (pintype "bidirectional"))
    )
    (net (code "116") (name "unconnected-(ACCEL-NC-Pad11)") (class "Default")
      (node (ref "ACCEL") (pin "11") (pinfunction "NC_11") (pintype "bidirectional"))
    )
    (net (code "117") (name "unconnected-(AIO_PO_CONNA-KL-Pad1)") (class "Default")
      (node (ref "AIO_PO_CONN") (pin "1") (pinfunction "KL_1") (pintype "passive"))
    )
    (net (code "118") (name "unconnected-(AIO_PO_CONNJ-KL-Pad3)") (class "Default")
      (node (ref "AIO_PO_CONN") (pin "3") (pinfunction "KL_3") (pintype "passive"))
    )
    (net (code "119") (name "unconnected-(IC1A-ST1{slash}2-Pad4)") (class "Default")
      (node (ref "IC1") (pin "4") (pinfunction "ST1/2_4") (pintype "input"))
    )
    (net (code "120") (name "unconnected-(IC1A-ST3{slash}4-Pad8)") (class "Default")
      (node (ref "IC1") (pin "8") (pinfunction "ST3/4_8") (pintype "input"))
    )
    (net (code "121") (name "unconnected-(IC2A-ST1{slash}2-Pad4)") (class "Default")
      (node (ref "IC2") (pin "4") (pinfunction "ST1/2_4") (pintype "input"))
    )
    (net (code "122") (name "unconnected-(IC2A-ST3{slash}4-Pad8)") (class "Default")
      (node (ref "IC2") (pin "8") (pinfunction "ST3/4_8") (pintype "input"))
    )
    (net (code "123") (name "unconnected-(IC3A-ST1{slash}2-Pad4)") (class "Default")
      (node (ref "IC3") (pin "4") (pinfunction "ST1/2_4") (pintype "input"))
    )
    (net (code "124") (name "unconnected-(IC3A-ST3{slash}4-Pad8)") (class "Default")
      (node (ref "IC3") (pin "8") (pinfunction "ST3/4_8") (pintype "input"))
    )
    (net (code "125") (name "unconnected-(SBRIO_ANALOG-DIO_0-PadP$44)") (class "Default")
      (node (ref "SBRIO_ANALOG") (pin "P$44") (pinfunction "DIO_0_P$44") (pintype "bidirectional"))
    )
    (net (code "126") (name "unconnected-(SBRIO_ANALOG-DIO_1-PadP$46)") (class "Default")
      (node (ref "SBRIO_ANALOG") (pin "P$46") (pinfunction "DIO_1_P$46") (pintype "bidirectional"))
    )
    (net (code "127") (name "unconnected-(SBRIO_ANALOG-DIO_2-PadP$48)") (class "Default")
      (node (ref "SBRIO_ANALOG") (pin "P$48") (pinfunction "DIO_2_P$48") (pintype "bidirectional"))
    )
    (net (code "128") (name "unconnected-(SBRIO_ANALOG-DIO_3-PadP$50)") (class "Default")
      (node (ref "SBRIO_ANALOG") (pin "P$50") (pinfunction "DIO_3_P$50") (pintype "bidirectional"))
    )
    (net (code "129") (name "unconnected-(SBRIO_AUX-DIO16-PadP$16)") (class "Default")
      (node (ref "SBRIO_AUX") (pin "P$16") (pinfunction "DIO16_P$16") (pintype "bidirectional"))
    )
    (net (code "130") (name "unconnected-(SBRIO_AUX-DIO17-PadP$14)") (class "Default")
      (node (ref "SBRIO_AUX") (pin "P$14") (pinfunction "DIO17_P$14") (pintype "bidirectional"))
    )
    (net (code "131") (name "unconnected-(SBRIO_AUX-DIO39-PadP$6)") (class "Default")
      (node (ref "SBRIO_AUX") (pin "P$6") (pinfunction "DIO39_P$6") (pintype "bidirectional"))
    )
    (net (code "132") (name "unconnected-(SBRIO_AUX-E-STOP-PadP$4)") (class "Default")
      (node (ref "SBRIO_AUX") (pin "P$4") (pinfunction "E-STOP_P$4") (pintype "bidirectional"))
    )
    (net (code "133") (name "unconnected-(SBRIO_AUX-LATCH-PadP$2)") (class "Default")
      (node (ref "SBRIO_AUX") (pin "P$2") (pinfunction "LATCH_P$2") (pintype "bidirectional"))
    )
    (net (code "134") (name "unconnected-(SBRIO_AUX-POS_AIR-PadP$1)") (class "Default")
      (node (ref "SBRIO_AUX") (pin "P$1") (pinfunction "POS_AIR_P$1") (pintype "bidirectional"))
    )
    (net (code "135") (name "unconnected-(SBRIO_MEZZANINE-DIO2-Pad210)") (class "Default")
      (node (ref "SBRIO_MEZZANINE") (pin "210") (pinfunction "DIO2_210") (pintype "bidirectional"))
    )
    (net (code "136") (name "unconnected-(SBRIO_MEZZANINE-DIO3-Pad198)") (class "Default")
      (node (ref "SBRIO_MEZZANINE") (pin "198") (pinfunction "DIO3_198") (pintype "bidirectional"))
    )
    (net (code "137") (name "unconnected-(SBRIO_MEZZANINE-DIO13-Pad108)") (class "Default")
      (node (ref "SBRIO_MEZZANINE") (pin "108") (pinfunction "DIO13_108") (pintype "bidirectional"))
    )
    (net (code "138") (name "unconnected-(SBRIO_MEZZANINE-DIO14-Pad102)") (class "Default")
      (node (ref "SBRIO_MEZZANINE") (pin "102") (pinfunction "DIO14_102") (pintype "bidirectional"))
    )
    (net (code "139") (name "unconnected-(SBRIO_MEZZANINE-DIO15-Pad90)") (class "Default")
      (node (ref "SBRIO_MEZZANINE") (pin "90") (pinfunction "DIO15_90") (pintype "bidirectional"))
    )
    (net (code "140") (name "unconnected-(SBRIO_MEZZANINE-DIO19-Pad207)") (class "Default")
      (node (ref "SBRIO_MEZZANINE") (pin "207") (pinfunction "DIO19_207") (pintype "bidirectional"))
    )
    (net (code "141") (name "unconnected-(SBRIO_MEZZANINE-DIO20-Pad195)") (class "Default")
      (node (ref "SBRIO_MEZZANINE") (pin "195") (pinfunction "DIO20_195") (pintype "bidirectional"))
    )
    (net (code "142") (name "unconnected-(SBRIO_MEZZANINE-DIO21-Pad189)") (class "Default")
      (node (ref "SBRIO_MEZZANINE") (pin "189") (pinfunction "DIO21_189") (pintype "bidirectional"))
    )
    (net (code "143") (name "unconnected-(SBRIO_MEZZANINE-DIO22-Pad177)") (class "Default")
      (node (ref "SBRIO_MEZZANINE") (pin "177") (pinfunction "DIO22_177") (pintype "bidirectional"))
    )
    (net (code "144") (name "unconnected-(SBRIO_MEZZANINE-DIO23-Pad171)") (class "Default")
      (node (ref "SBRIO_MEZZANINE") (pin "171") (pinfunction "DIO23_171") (pintype "bidirectional"))
    )
    (net (code "145") (name "unconnected-(SBRIO_MEZZANINE-DIO24-Pad159)") (class "Default")
      (node (ref "SBRIO_MEZZANINE") (pin "159") (pinfunction "DIO24_159") (pintype "bidirectional"))
    )
    (net (code "146") (name "unconnected-(SBRIO_MEZZANINE-DIO25-Pad153)") (class "Default")
      (node (ref "SBRIO_MEZZANINE") (pin "153") (pinfunction "DIO25_153") (pintype "bidirectional"))
    )
    (net (code "147") (name "unconnected-(SBRIO_MEZZANINE-DIO26-Pad141)") (class "Default")
      (node (ref "SBRIO_MEZZANINE") (pin "141") (pinfunction "DIO26_141") (pintype "bidirectional"))
    )
    (net (code "148") (name "unconnected-(SBRIO_MEZZANINE-DIO27-Pad135)") (class "Default")
      (node (ref "SBRIO_MEZZANINE") (pin "135") (pinfunction "DIO27_135") (pintype "bidirectional"))
    )
    (net (code "149") (name "unconnected-(SBRIO_MEZZANINE-DIO28-Pad123)") (class "Default")
      (node (ref "SBRIO_MEZZANINE") (pin "123") (pinfunction "DIO28_123") (pintype "bidirectional"))
    )
    (net (code "150") (name "unconnected-(SBRIO_MEZZANINE-DIO29-Pad117)") (class "Default")
      (node (ref "SBRIO_MEZZANINE") (pin "117") (pinfunction "DIO29_117") (pintype "bidirectional"))
    )
    (net (code "151") (name "unconnected-(SBRIO_MEZZANINE-DIO30-Pad105)") (class "Default")
      (node (ref "SBRIO_MEZZANINE") (pin "105") (pinfunction "DIO30_105") (pintype "bidirectional"))
    )
    (net (code "152") (name "unconnected-(SBRIO_MEZZANINE-DIO31-Pad99)") (class "Default")
      (node (ref "SBRIO_MEZZANINE") (pin "99") (pinfunction "DIO31_99") (pintype "bidirectional"))
    )
    (net (code "153") (name "unconnected-(SBRIO_MEZZANINE-DIO33-Pad215)") (class "Default")
      (node (ref "SBRIO_MEZZANINE") (pin "215") (pinfunction "DIO33_215") (pintype "bidirectional"))
    )
    (net (code "154") (name "unconnected-(SBRIO_MEZZANINE-DIO34-Pad203)") (class "Default")
      (node (ref "SBRIO_MEZZANINE") (pin "203") (pinfunction "DIO34_203") (pintype "bidirectional"))
    )
    (net (code "155") (name "unconnected-(SBRIO_MEZZANINE-DIO35-Pad197)") (class "Default")
      (node (ref "SBRIO_MEZZANINE") (pin "197") (pinfunction "DIO35_197") (pintype "bidirectional"))
    )
    (net (code "156") (name "unconnected-(SBRIO_MEZZANINE-DIO36-Pad185)") (class "Default")
      (node (ref "SBRIO_MEZZANINE") (pin "185") (pinfunction "DIO36_185") (pintype "bidirectional"))
    )
    (net (code "157") (name "unconnected-(SBRIO_MEZZANINE-DIO46-Pad95)") (class "Default")
      (node (ref "SBRIO_MEZZANINE") (pin "95") (pinfunction "DIO46_95") (pintype "bidirectional"))
    )
    (net (code "158") (name "unconnected-(SBRIO_MEZZANINE-DIO47-Pad89)") (class "Default")
      (node (ref "SBRIO_MEZZANINE") (pin "89") (pinfunction "DIO47_89") (pintype "bidirectional"))
    )
    (net (code "159") (name "unconnected-(SBRIO_MEZZANINE-DIO49-Pad218)") (class "Default")
      (node (ref "SBRIO_MEZZANINE") (pin "218") (pinfunction "DIO49_218") (pintype "bidirectional"))
    )
    (net (code "160") (name "unconnected-(SBRIO_MEZZANINE-DIO50-Pad212)") (class "Default")
      (node (ref "SBRIO_MEZZANINE") (pin "212") (pinfunction "DIO50_212") (pintype "bidirectional"))
    )
    (net (code "161") (name "unconnected-(SBRIO_MEZZANINE-DIO51-Pad200)") (class "Default")
      (node (ref "SBRIO_MEZZANINE") (pin "200") (pinfunction "DIO51_200") (pintype "bidirectional"))
    )
    (net (code "162") (name "unconnected-(SBRIO_MEZZANINE-DIO52-Pad194)") (class "Default")
      (node (ref "SBRIO_MEZZANINE") (pin "194") (pinfunction "DIO52_194") (pintype "bidirectional"))
    )
    (net (code "163") (name "unconnected-(SBRIO_MEZZANINE-DIO53-Pad182)") (class "Default")
      (node (ref "SBRIO_MEZZANINE") (pin "182") (pinfunction "DIO53_182") (pintype "bidirectional"))
    )
    (net (code "164") (name "unconnected-(SBRIO_MEZZANINE-DIO54-Pad176)") (class "Default")
      (node (ref "SBRIO_MEZZANINE") (pin "176") (pinfunction "DIO54_176") (pintype "bidirectional"))
    )
    (net (code "165") (name "unconnected-(SBRIO_MEZZANINE-DIO55-Pad164)") (class "Default")
      (node (ref "SBRIO_MEZZANINE") (pin "164") (pinfunction "DIO55_164") (pintype "bidirectional"))
    )
    (net (code "166") (name "unconnected-(SBRIO_MEZZANINE-DIO56-Pad158)") (class "Default")
      (node (ref "SBRIO_MEZZANINE") (pin "158") (pinfunction "DIO56_158") (pintype "bidirectional"))
    )
    (net (code "167") (name "unconnected-(SBRIO_MEZZANINE-DIO57-Pad146)") (class "Default")
      (node (ref "SBRIO_MEZZANINE") (pin "146") (pinfunction "DIO57_146") (pintype "bidirectional"))
    )
    (net (code "168") (name "unconnected-(SBRIO_MEZZANINE-DIO58-Pad140)") (class "Default")
      (node (ref "SBRIO_MEZZANINE") (pin "140") (pinfunction "DIO58_140") (pintype "bidirectional"))
    )
    (net (code "169") (name "unconnected-(SBRIO_MEZZANINE-DIO59-Pad128)") (class "Default")
      (node (ref "SBRIO_MEZZANINE") (pin "128") (pinfunction "DIO59_128") (pintype "bidirectional"))
    )
    (net (code "170") (name "unconnected-(SBRIO_MEZZANINE-DIO60-Pad122)") (class "Default")
      (node (ref "SBRIO_MEZZANINE") (pin "122") (pinfunction "DIO60_122") (pintype "bidirectional"))
    )
    (net (code "171") (name "unconnected-(SBRIO_MEZZANINE-DIO61-Pad110)") (class "Default")
      (node (ref "SBRIO_MEZZANINE") (pin "110") (pinfunction "DIO61_110") (pintype "bidirectional"))
    )
    (net (code "172") (name "unconnected-(SBRIO_MEZZANINE-DIO62-Pad104)") (class "Default")
      (node (ref "SBRIO_MEZZANINE") (pin "104") (pinfunction "DIO62_104") (pintype "bidirectional"))
    )
    (net (code "173") (name "unconnected-(SBRIO_MEZZANINE-DIO63-Pad92)") (class "Default")
      (node (ref "SBRIO_MEZZANINE") (pin "92") (pinfunction "DIO63_92") (pintype "bidirectional"))
    )
    (net (code "174") (name "unconnected-(SBRIO_MEZZANINE-DIO66-Pad208)") (class "Default")
      (node (ref "SBRIO_MEZZANINE") (pin "208") (pinfunction "DIO66_208") (pintype "bidirectional"))
    )
    (net (code "175") (name "unconnected-(SBRIO_MEZZANINE-DIO67-Pad202)") (class "Default")
      (node (ref "SBRIO_MEZZANINE") (pin "202") (pinfunction "DIO67_202") (pintype "bidirectional"))
    )
    (net (code "176") (name "unconnected-(SBRIO_MEZZANINE-DIO68-Pad190)") (class "Default")
      (node (ref "SBRIO_MEZZANINE") (pin "190") (pinfunction "DIO68_190") (pintype "bidirectional"))
    )
    (net (code "177") (name "unconnected-(SBRIO_MEZZANINE-DIO69-Pad184)") (class "Default")
      (node (ref "SBRIO_MEZZANINE") (pin "184") (pinfunction "DIO69_184") (pintype "bidirectional"))
    )
    (net (code "178") (name "unconnected-(SBRIO_MEZZANINE-DIO70-Pad172)") (class "Default")
      (node (ref "SBRIO_MEZZANINE") (pin "172") (pinfunction "DIO70_172") (pintype "bidirectional"))
    )
    (net (code "179") (name "unconnected-(SBRIO_MEZZANINE-DIO71-Pad166)") (class "Default")
      (node (ref "SBRIO_MEZZANINE") (pin "166") (pinfunction "DIO71_166") (pintype "bidirectional"))
    )
    (net (code "180") (name "unconnected-(SBRIO_MEZZANINE-DIO72-Pad154)") (class "Default")
      (node (ref "SBRIO_MEZZANINE") (pin "154") (pinfunction "DIO72_154") (pintype "bidirectional"))
    )
    (net (code "181") (name "unconnected-(SBRIO_MEZZANINE-DIO73-Pad148)") (class "Default")
      (node (ref "SBRIO_MEZZANINE") (pin "148") (pinfunction "DIO73_148") (pintype "bidirectional"))
    )
    (net (code "182") (name "unconnected-(SBRIO_MEZZANINE-DIO74-Pad136)") (class "Default")
      (node (ref "SBRIO_MEZZANINE") (pin "136") (pinfunction "DIO74_136") (pintype "bidirectional"))
    )
    (net (code "183") (name "unconnected-(SBRIO_MEZZANINE-DIO75-Pad130)") (class "Default")
      (node (ref "SBRIO_MEZZANINE") (pin "130") (pinfunction "DIO75_130") (pintype "bidirectional"))
    )
    (net (code "184") (name "unconnected-(SBRIO_MEZZANINE-DIO76-Pad118)") (class "Default")
      (node (ref "SBRIO_MEZZANINE") (pin "118") (pinfunction "DIO76_118") (pintype "bidirectional"))
    )
    (net (code "185") (name "unconnected-(SBRIO_MEZZANINE-DIO77-Pad112)") (class "Default")
      (node (ref "SBRIO_MEZZANINE") (pin "112") (pinfunction "DIO77_112") (pintype "bidirectional"))
    )
    (net (code "186") (name "unconnected-(SBRIO_MEZZANINE-DIO78-Pad100)") (class "Default")
      (node (ref "SBRIO_MEZZANINE") (pin "100") (pinfunction "DIO78_100") (pintype "bidirectional"))
    )
    (net (code "187") (name "unconnected-(SBRIO_MEZZANINE-DIO79-Pad94)") (class "Default")
      (node (ref "SBRIO_MEZZANINE") (pin "94") (pinfunction "DIO79_94") (pintype "bidirectional"))
    )
    (net (code "188") (name "unconnected-(SBRIO_MEZZANINE-DIO80-Pad235)") (class "Default")
      (node (ref "SBRIO_MEZZANINE") (pin "235") (pinfunction "DIO80_235") (pintype "bidirectional"))
    )
    (net (code "189") (name "unconnected-(SBRIO_MEZZANINE-DIO82-Pad217)") (class "Default")
      (node (ref "SBRIO_MEZZANINE") (pin "217") (pinfunction "DIO82_217") (pintype "bidirectional"))
    )
    (net (code "190") (name "unconnected-(SBRIO_MEZZANINE-DIO84-Pad199)") (class "Default")
      (node (ref "SBRIO_MEZZANINE") (pin "199") (pinfunction "DIO84_199") (pintype "bidirectional"))
    )
    (net (code "191") (name "unconnected-(SBRIO_MEZZANINE-DIO89-Pad151)") (class "Default")
      (node (ref "SBRIO_MEZZANINE") (pin "151") (pinfunction "DIO89_151") (pintype "bidirectional"))
    )
    (net (code "192") (name "unconnected-(U1-A2-PadP$4)") (class "Default")
      (node (ref "U1") (pin "P$4") (pinfunction "A2_P$4") (pintype "bidirectional"))
    )
    (net (code "193") (name "unconnected-(U1-B2-PadP$1)") (class "Default")
      (node (ref "U1") (pin "P$1") (pinfunction "B2_P$1") (pintype "bidirectional"))
    )
  )
)
